# ProPrj_FaderBay_2025-03-18.net
KiCad netlist of a schematic drawn in EasyEDA Pro
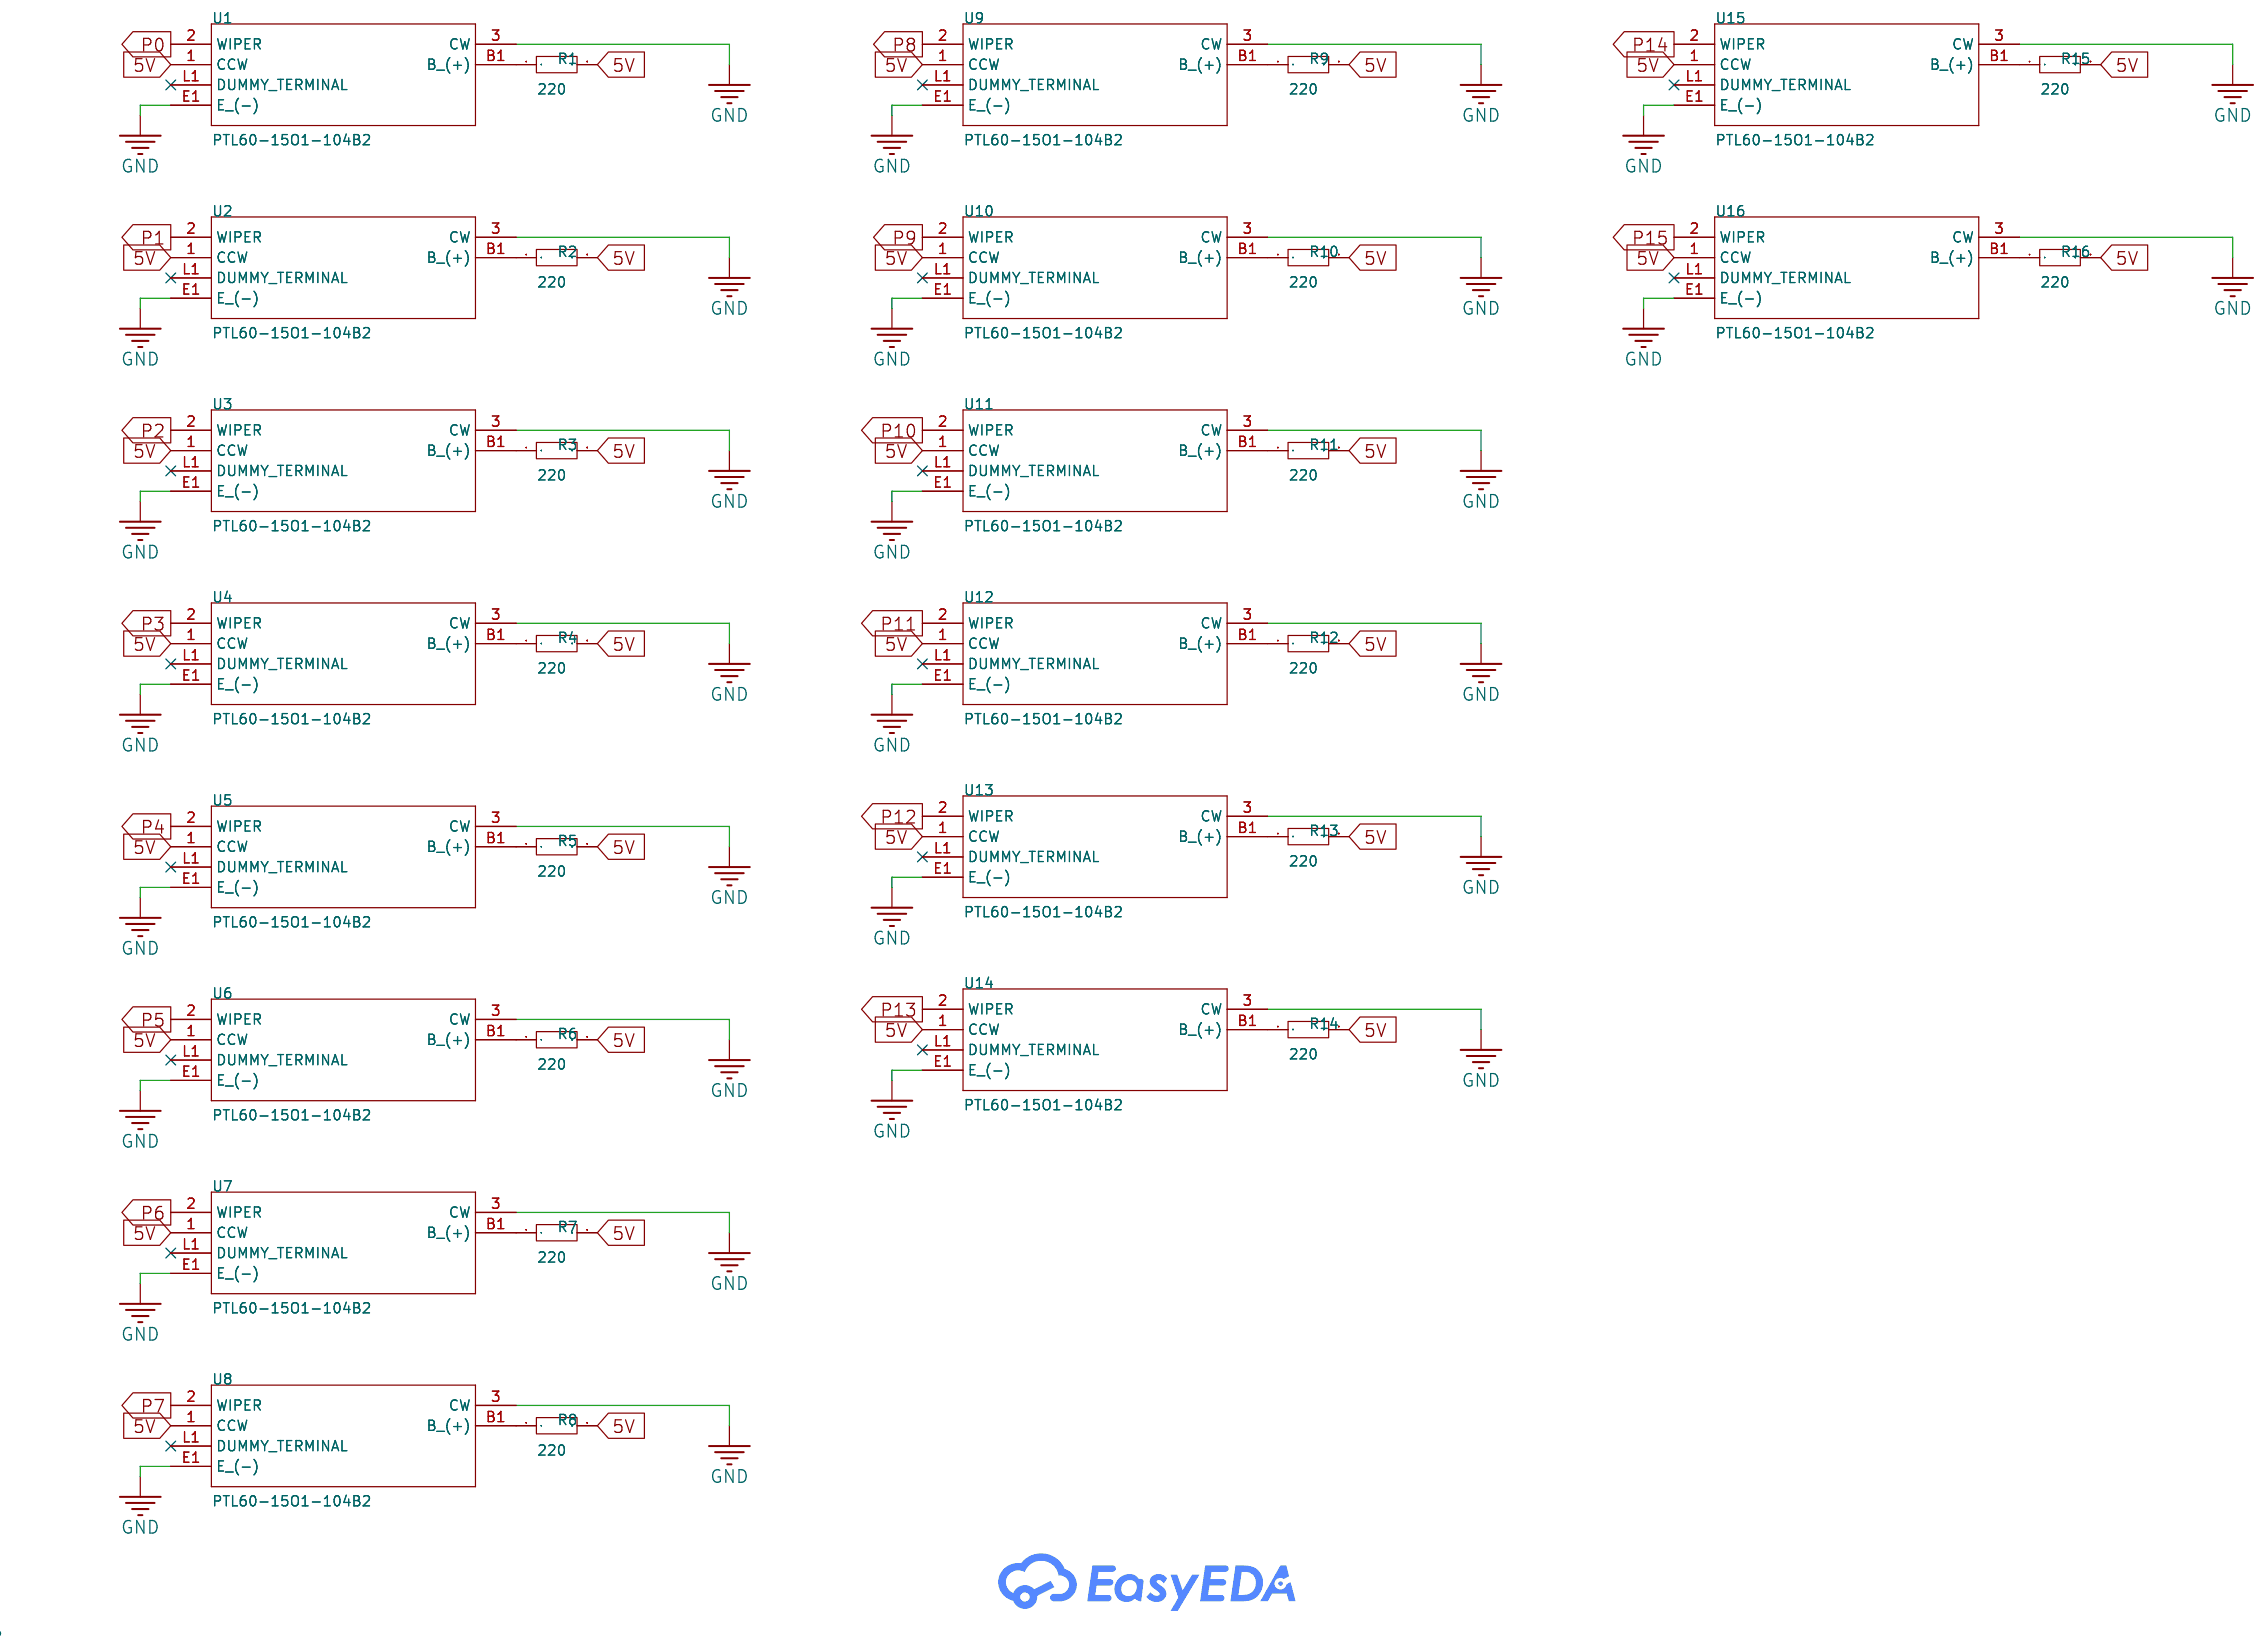
[diagram p0: P1]
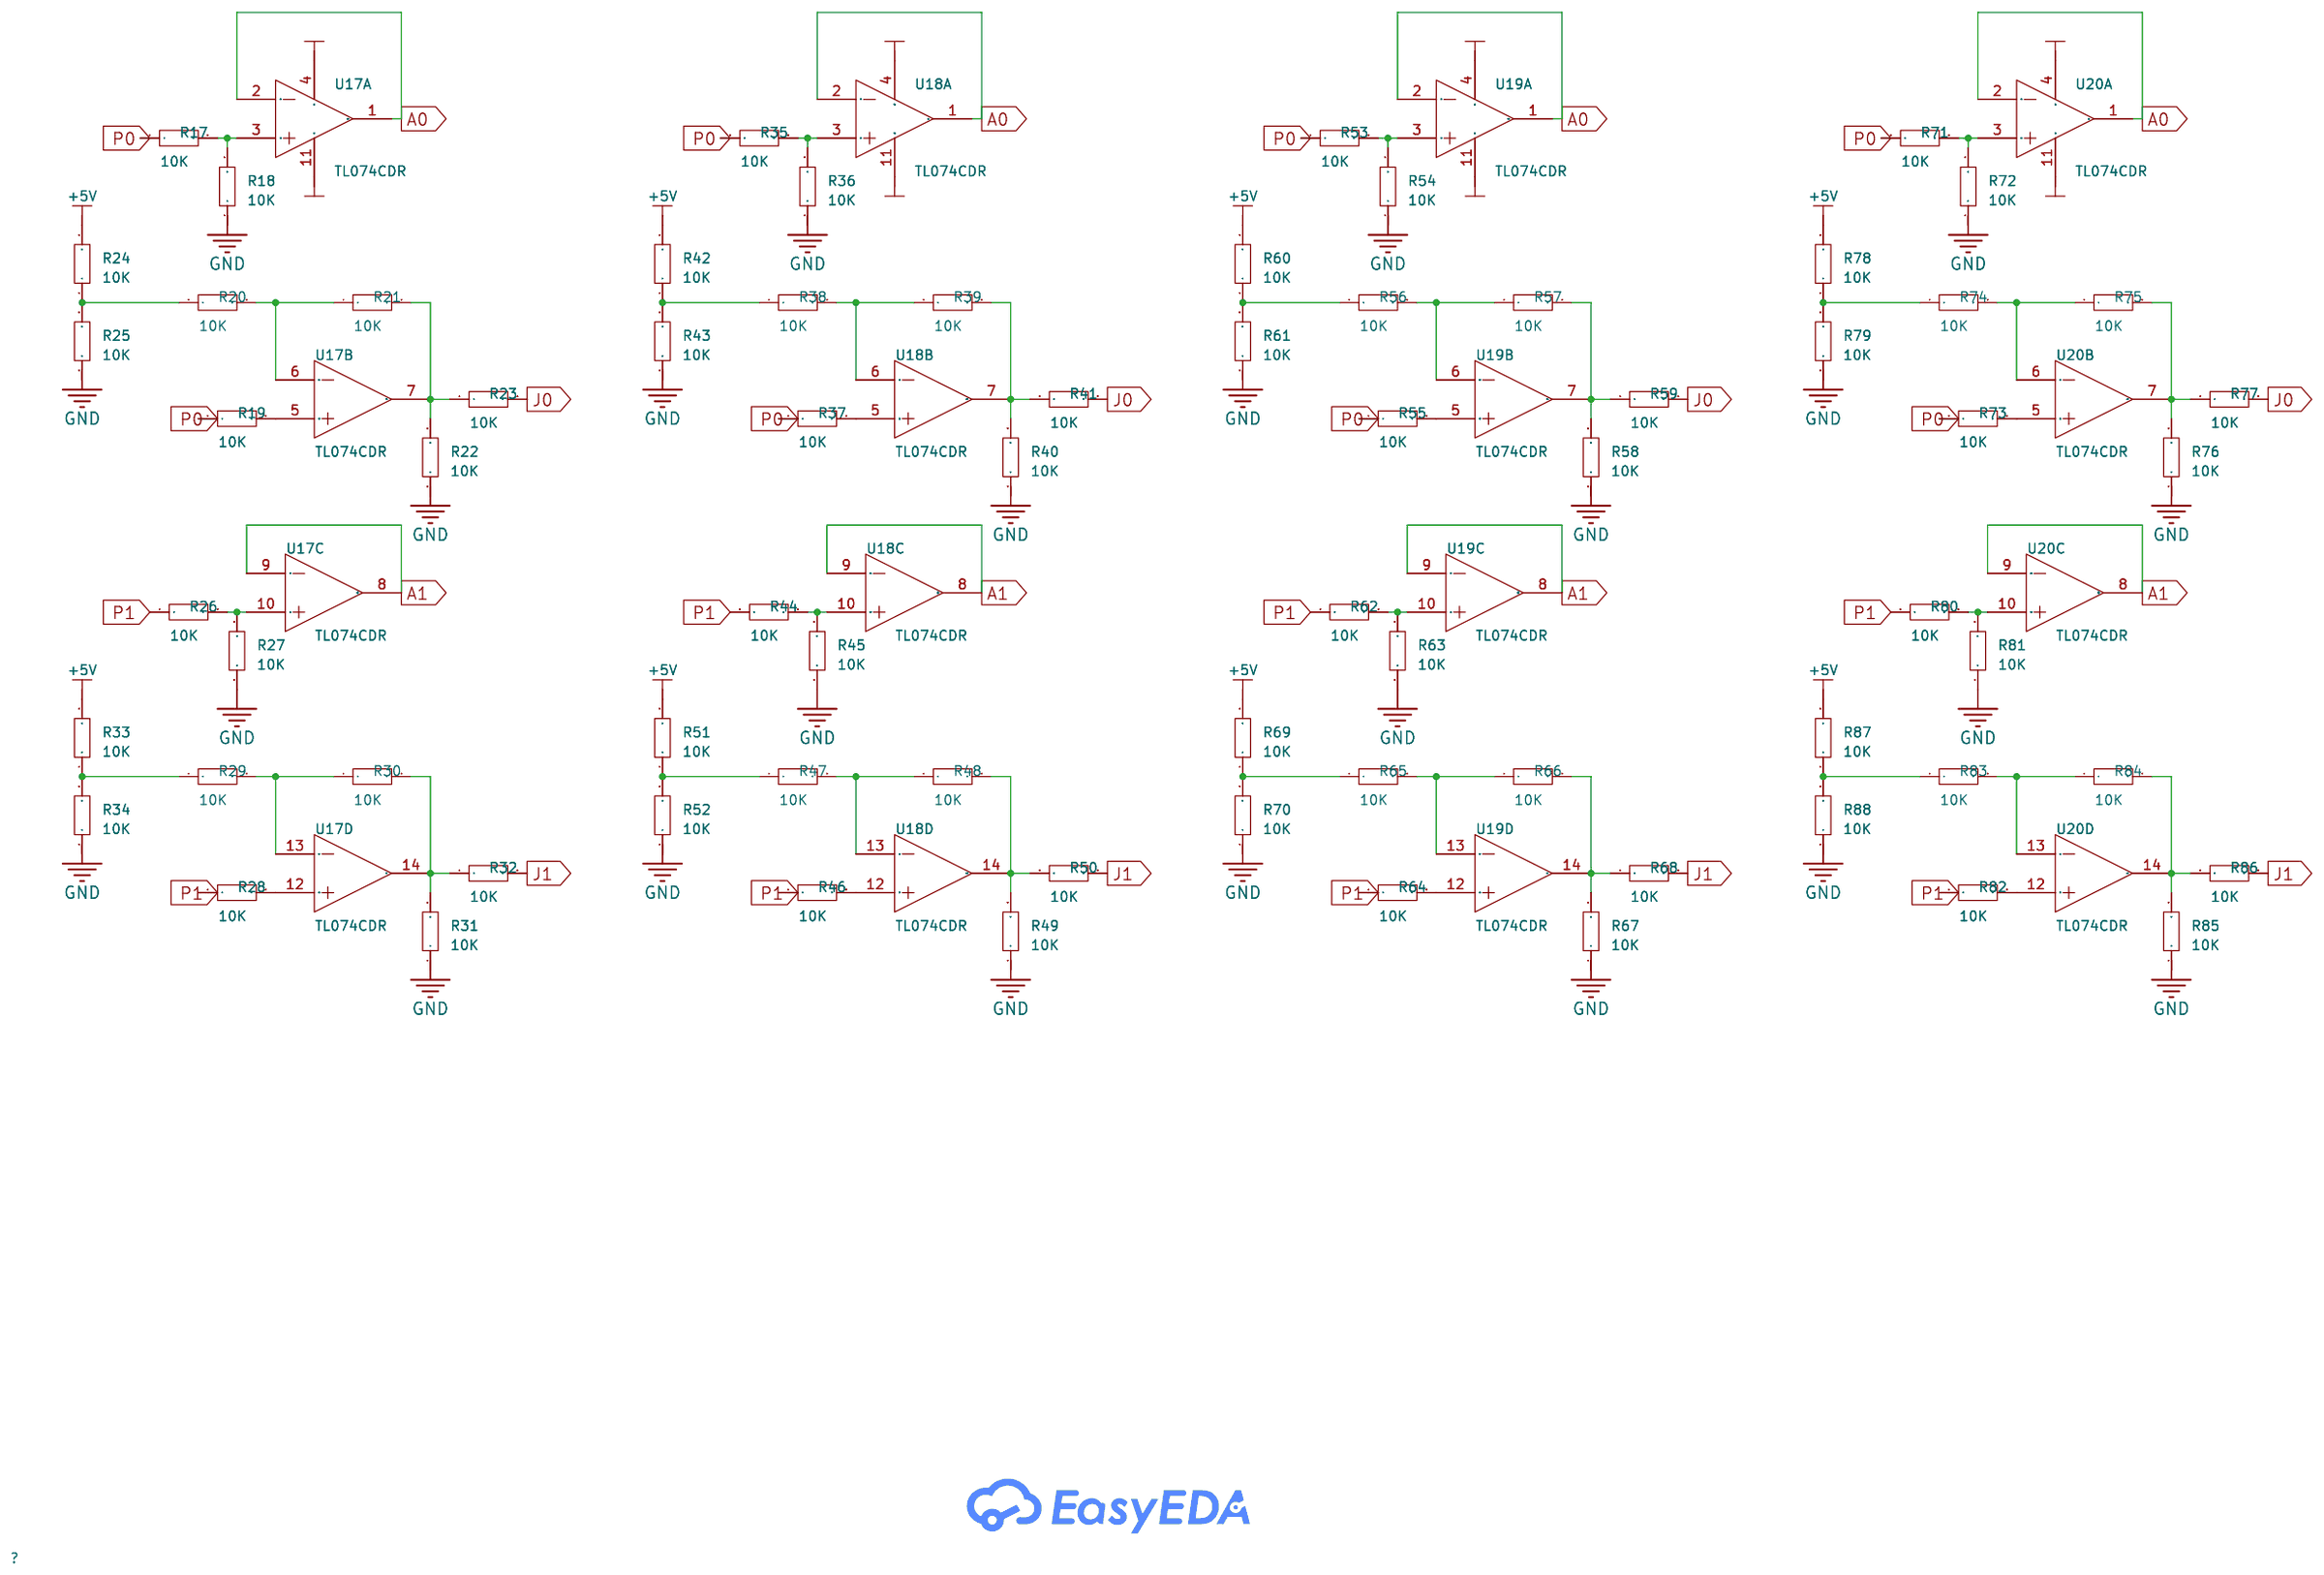
[diagram p1: P2]
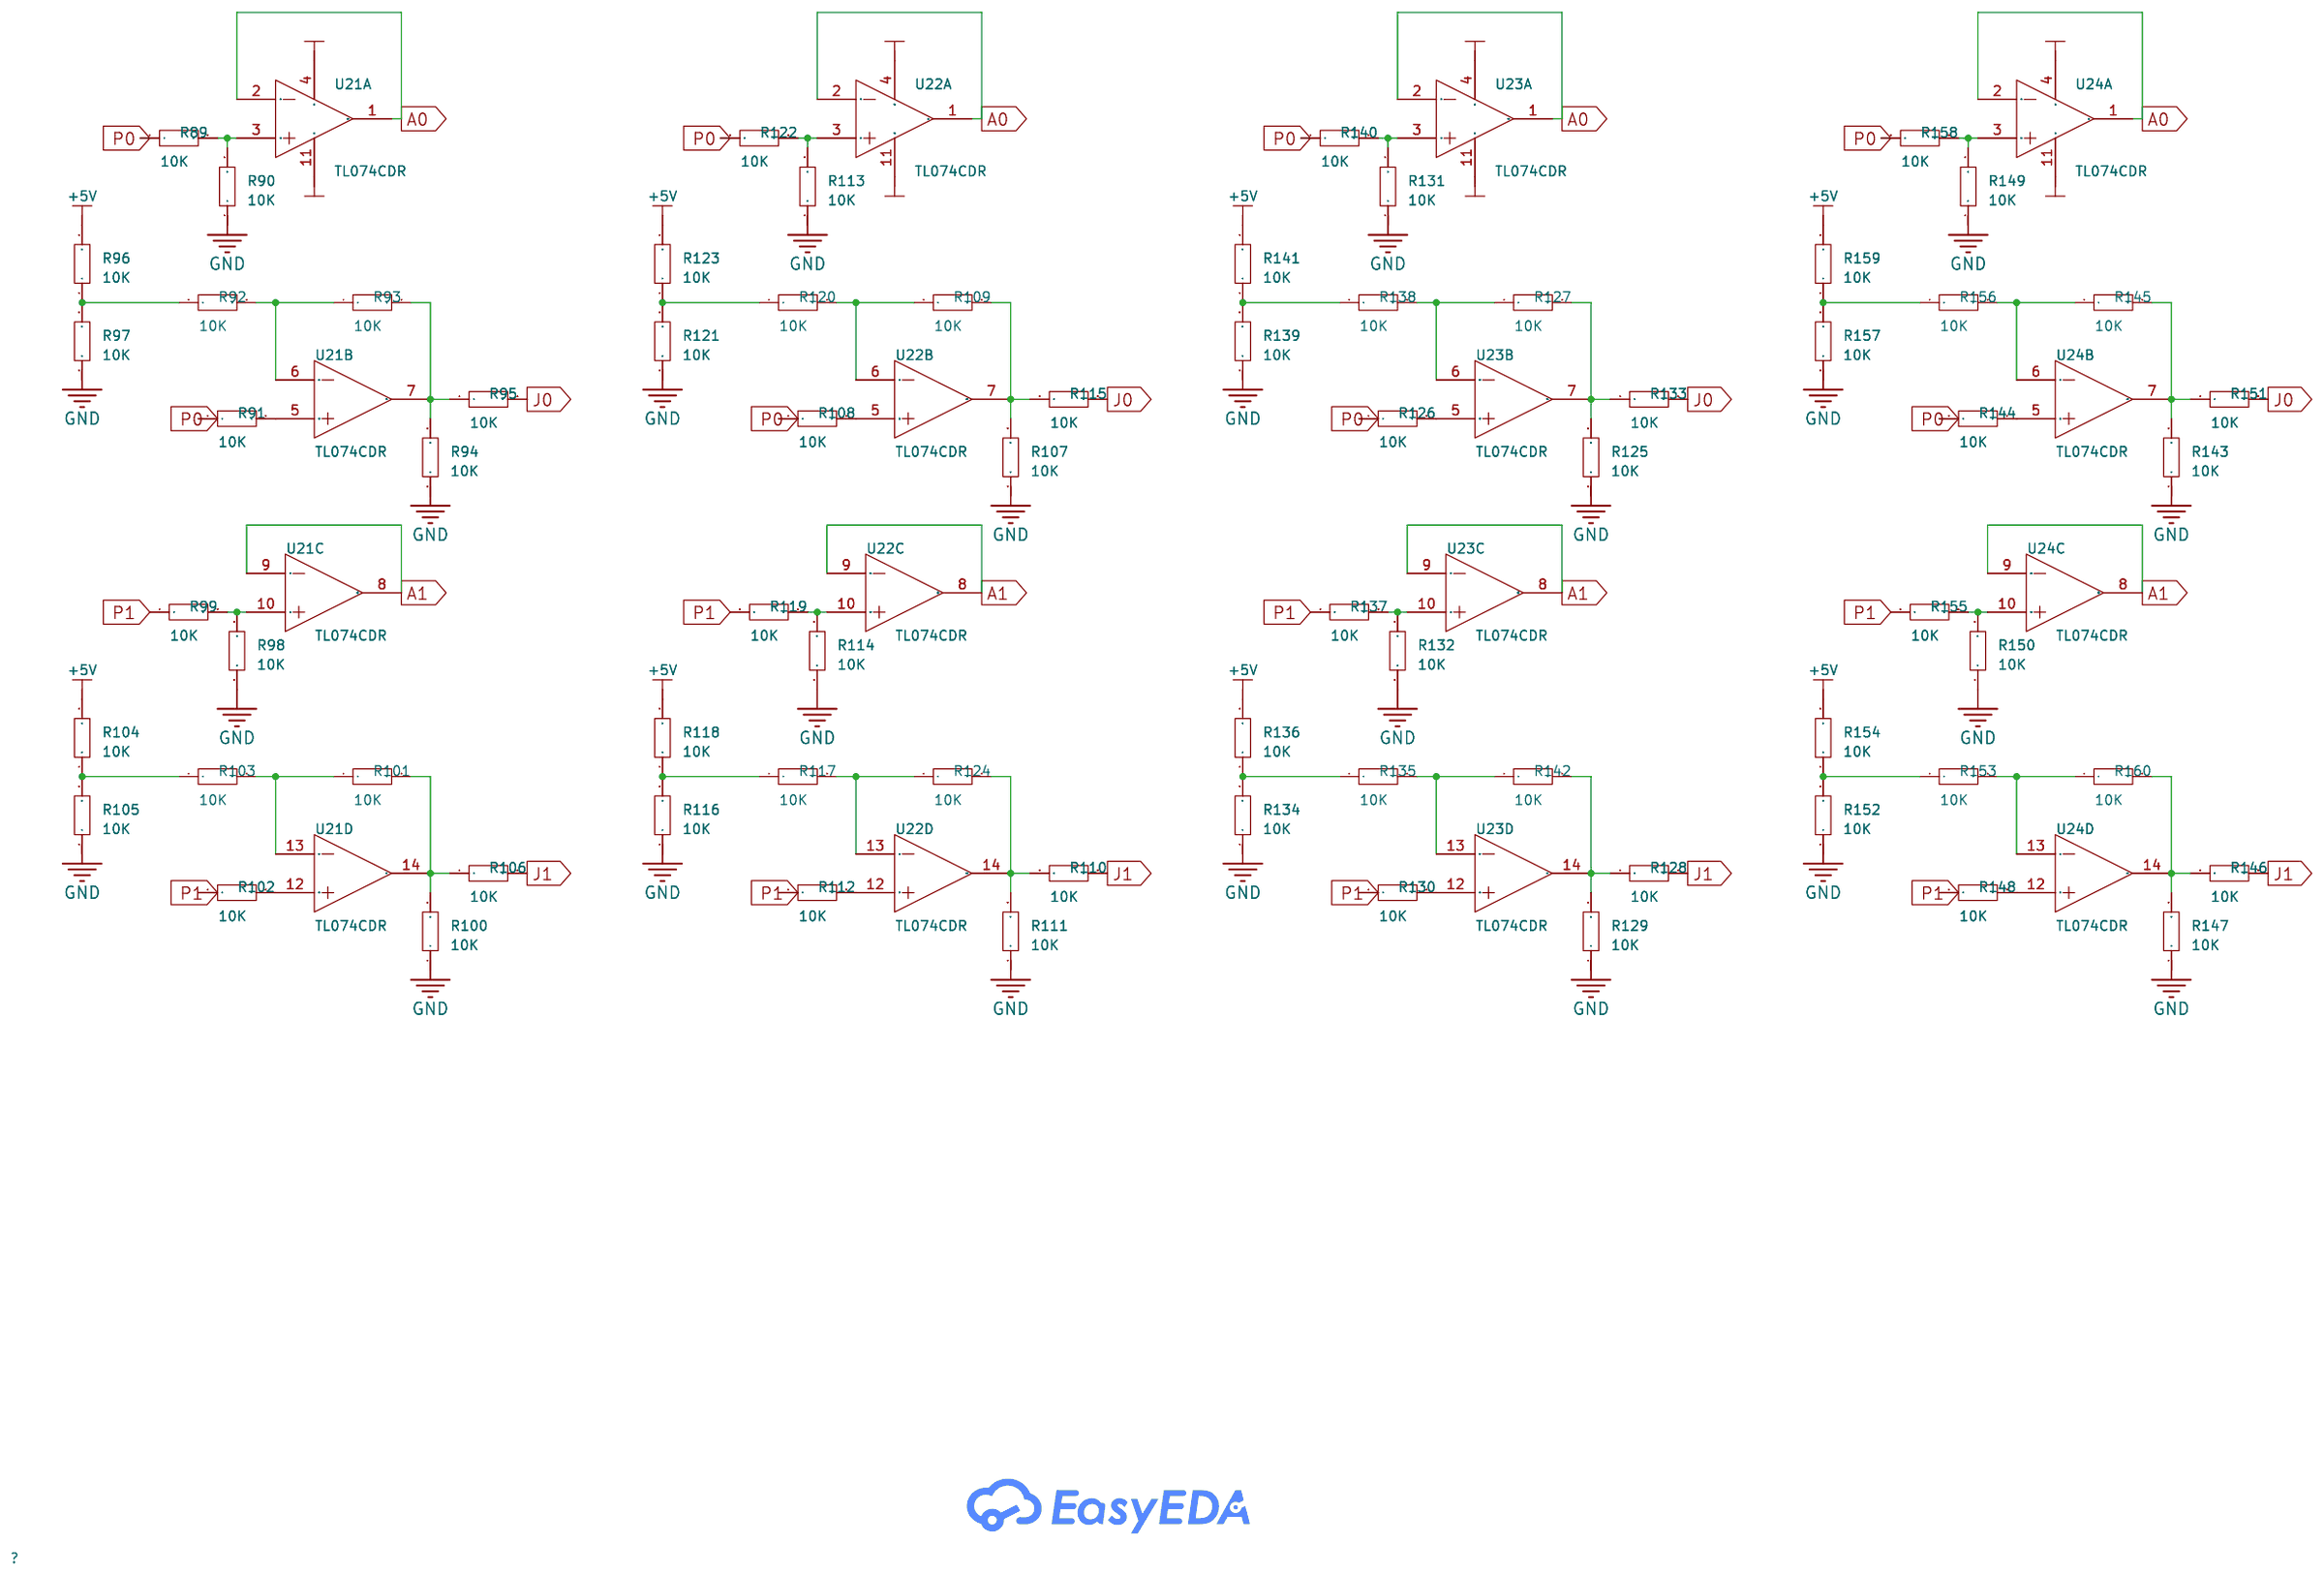
[diagram p2: P3]

(export (version "E")
  (design (tool "Eeschema 10.0.6"))
  (components
    (comp (ref "R1") (value "220") (footprint "easyedapro:R0603") (libsource (lib "easyedapro") (part "Res")))
    (comp (ref "R2") (value "220") (footprint "easyedapro:R0603") (libsource (lib "easyedapro") (part "Res")))
    (comp (ref "R3") (value "220") (footprint "easyedapro:R0603") (libsource (lib "easyedapro") (part "Res")))
    (comp (ref "R4") (value "220") (footprint "easyedapro:R0603") (libsource (lib "easyedapro") (part "Res")))
    (comp (ref "R5") (value "220") (footprint "easyedapro:R0603") (libsource (lib "easyedapro") (part "Res")))
    (comp (ref "R6") (value "220") (footprint "easyedapro:R0603") (libsource (lib "easyedapro") (part "Res")))
    (comp (ref "R7") (value "220") (footprint "easyedapro:R0603") (libsource (lib "easyedapro") (part "Res")))
    (comp (ref "R8") (value "220") (footprint "easyedapro:R0603") (libsource (lib "easyedapro") (part "Res")))
    (comp (ref "R9") (value "220") (footprint "easyedapro:R0603") (libsource (lib "easyedapro") (part "Res")))
    (comp (ref "R10")
      (value "220")
      (footprint "easyedapro:R0603")
      (libsource (lib "easyedapro") (part "Res"))
    )
    (comp (ref "R11")
      (value "220")
      (footprint "easyedapro:R0603")
      (libsource (lib "easyedapro") (part "Res"))
    )
    (comp (ref "R12")
      (value "220")
      (footprint "easyedapro:R0603")
      (libsource (lib "easyedapro") (part "Res"))
    )
    (comp (ref "R13")
      (value "220")
      (footprint "easyedapro:R0603")
      (libsource (lib "easyedapro") (part "Res"))
    )
    (comp (ref "R14")
      (value "220")
      (footprint "easyedapro:R0603")
      (libsource (lib "easyedapro") (part "Res"))
    )
    (comp (ref "R15")
      (value "220")
      (footprint "easyedapro:R0603")
      (libsource (lib "easyedapro") (part "Res"))
    )
    (comp (ref "R16")
      (value "220")
      (footprint "easyedapro:R0603")
      (libsource (lib "easyedapro") (part "Res"))
    )
    (comp (ref "U1")
      (value "PTL60-15O1-104B2")
      (footprint "easyedapro:PTL6015O1104B2")
      (libsource (lib "easyedapro") (part "PTL60-15O1-104B2"))
    )
    (comp (ref "U2")
      (value "PTL60-15O1-104B2")
      (footprint "easyedapro:PTL6015O1104B2")
      (libsource (lib "easyedapro") (part "PTL60-15O1-104B2"))
    )
    (comp (ref "U3")
      (value "PTL60-15O1-104B2")
      (footprint "easyedapro:PTL6015O1104B2")
      (libsource (lib "easyedapro") (part "PTL60-15O1-104B2"))
    )
    (comp (ref "U4")
      (value "PTL60-15O1-104B2")
      (footprint "easyedapro:PTL6015O1104B2")
      (libsource (lib "easyedapro") (part "PTL60-15O1-104B2"))
    )
    (comp (ref "U5")
      (value "PTL60-15O1-104B2")
      (footprint "easyedapro:PTL6015O1104B2")
      (libsource (lib "easyedapro") (part "PTL60-15O1-104B2"))
    )
    (comp (ref "U6")
      (value "PTL60-15O1-104B2")
      (footprint "easyedapro:PTL6015O1104B2")
      (libsource (lib "easyedapro") (part "PTL60-15O1-104B2"))
    )
    (comp (ref "U7")
      (value "PTL60-15O1-104B2")
      (footprint "easyedapro:PTL6015O1104B2")
      (libsource (lib "easyedapro") (part "PTL60-15O1-104B2"))
    )
    (comp (ref "U8")
      (value "PTL60-15O1-104B2")
      (footprint "easyedapro:PTL6015O1104B2")
      (libsource (lib "easyedapro") (part "PTL60-15O1-104B2"))
    )
    (comp (ref "U9")
      (value "PTL60-15O1-104B2")
      (footprint "easyedapro:PTL6015O1104B2")
      (libsource (lib "easyedapro") (part "PTL60-15O1-104B2"))
    )
    (comp (ref "U10")
      (value "PTL60-15O1-104B2")
      (footprint "easyedapro:PTL6015O1104B2")
      (libsource (lib "easyedapro") (part "PTL60-15O1-104B2"))
    )
    (comp (ref "U11")
      (value "PTL60-15O1-104B2")
      (footprint "easyedapro:PTL6015O1104B2")
      (libsource (lib "easyedapro") (part "PTL60-15O1-104B2"))
    )
    (comp (ref "U12")
      (value "PTL60-15O1-104B2")
      (footprint "easyedapro:PTL6015O1104B2")
      (libsource (lib "easyedapro") (part "PTL60-15O1-104B2"))
    )
    (comp (ref "U13")
      (value "PTL60-15O1-104B2")
      (footprint "easyedapro:PTL6015O1104B2")
      (libsource (lib "easyedapro") (part "PTL60-15O1-104B2"))
    )
    (comp (ref "U14")
      (value "PTL60-15O1-104B2")
      (footprint "easyedapro:PTL6015O1104B2")
      (libsource (lib "easyedapro") (part "PTL60-15O1-104B2"))
    )
    (comp (ref "U15")
      (value "PTL60-15O1-104B2")
      (footprint "easyedapro:PTL6015O1104B2")
      (libsource (lib "easyedapro") (part "PTL60-15O1-104B2"))
    )
    (comp (ref "U16")
      (value "PTL60-15O1-104B2")
      (footprint "easyedapro:PTL6015O1104B2")
      (libsource (lib "easyedapro") (part "PTL60-15O1-104B2"))
    )
    (comp (ref "R17")
      (value "10K")
      (footprint "easyedapro:R0603")
      (libsource (lib "easyedapro") (part "Res"))
    )
    (comp (ref "R18")
      (value "10K")
      (footprint "easyedapro:R0603")
      (libsource (lib "easyedapro") (part "Res"))
    )
    (comp (ref "R19")
      (value "10K")
      (footprint "easyedapro:R0603")
      (libsource (lib "easyedapro") (part "Res"))
    )
    (comp (ref "R20")
      (value "10K")
      (footprint "easyedapro:R0603")
      (libsource (lib "easyedapro") (part "Res"))
    )
    (comp (ref "R21")
      (value "10K")
      (footprint "easyedapro:R0603")
      (libsource (lib "easyedapro") (part "Res"))
    )
    (comp (ref "R22")
      (value "10K")
      (footprint "easyedapro:R0603")
      (libsource (lib "easyedapro") (part "Res"))
    )
    (comp (ref "R23")
      (value "10K")
      (footprint "easyedapro:R0603")
      (libsource (lib "easyedapro") (part "Res"))
    )
    (comp (ref "R24")
      (value "10K")
      (footprint "easyedapro:R0603")
      (libsource (lib "easyedapro") (part "Res"))
    )
    (comp (ref "R25")
      (value "10K")
      (footprint "easyedapro:R0603")
      (libsource (lib "easyedapro") (part "Res"))
    )
    (comp (ref "R26")
      (value "10K")
      (footprint "easyedapro:R0603")
      (libsource (lib "easyedapro") (part "Res"))
    )
    (comp (ref "R27")
      (value "10K")
      (footprint "easyedapro:R0603")
      (libsource (lib "easyedapro") (part "Res"))
    )
    (comp (ref "R28")
      (value "10K")
      (footprint "easyedapro:R0603")
      (libsource (lib "easyedapro") (part "Res"))
    )
    (comp (ref "R29")
      (value "10K")
      (footprint "easyedapro:R0603")
      (libsource (lib "easyedapro") (part "Res"))
    )
    (comp (ref "R30")
      (value "10K")
      (footprint "easyedapro:R0603")
      (libsource (lib "easyedapro") (part "Res"))
    )
    (comp (ref "R31")
      (value "10K")
      (footprint "easyedapro:R0603")
      (libsource (lib "easyedapro") (part "Res"))
    )
    (comp (ref "R32")
      (value "10K")
      (footprint "easyedapro:R0603")
      (libsource (lib "easyedapro") (part "Res"))
    )
    (comp (ref "R33")
      (value "10K")
      (footprint "easyedapro:R0603")
      (libsource (lib "easyedapro") (part "Res"))
    )
    (comp (ref "R34")
      (value "10K")
      (footprint "easyedapro:R0603")
      (libsource (lib "easyedapro") (part "Res"))
    )
    (comp (ref "R35")
      (value "10K")
      (footprint "easyedapro:R0603")
      (libsource (lib "easyedapro") (part "Res"))
    )
    (comp (ref "R36")
      (value "10K")
      (footprint "easyedapro:R0603")
      (libsource (lib "easyedapro") (part "Res"))
    )
    (comp (ref "R37")
      (value "10K")
      (footprint "easyedapro:R0603")
      (libsource (lib "easyedapro") (part "Res"))
    )
    (comp (ref "R38")
      (value "10K")
      (footprint "easyedapro:R0603")
      (libsource (lib "easyedapro") (part "Res"))
    )
    (comp (ref "R39")
      (value "10K")
      (footprint "easyedapro:R0603")
      (libsource (lib "easyedapro") (part "Res"))
    )
    (comp (ref "R40")
      (value "10K")
      (footprint "easyedapro:R0603")
      (libsource (lib "easyedapro") (part "Res"))
    )
    (comp (ref "R41")
      (value "10K")
      (footprint "easyedapro:R0603")
      (libsource (lib "easyedapro") (part "Res"))
    )
    (comp (ref "R42")
      (value "10K")
      (footprint "easyedapro:R0603")
      (libsource (lib "easyedapro") (part "Res"))
    )
    (comp (ref "R43")
      (value "10K")
      (footprint "easyedapro:R0603")
      (libsource (lib "easyedapro") (part "Res"))
    )
    (comp (ref "R44")
      (value "10K")
      (footprint "easyedapro:R0603")
      (libsource (lib "easyedapro") (part "Res"))
    )
    (comp (ref "R45")
      (value "10K")
      (footprint "easyedapro:R0603")
      (libsource (lib "easyedapro") (part "Res"))
    )
    (comp (ref "R46")
      (value "10K")
      (footprint "easyedapro:R0603")
      (libsource (lib "easyedapro") (part "Res"))
    )
    (comp (ref "R47")
      (value "10K")
      (footprint "easyedapro:R0603")
      (libsource (lib "easyedapro") (part "Res"))
    )
    (comp (ref "R48")
      (value "10K")
      (footprint "easyedapro:R0603")
      (libsource (lib "easyedapro") (part "Res"))
    )
    (comp (ref "R49")
      (value "10K")
      (footprint "easyedapro:R0603")
      (libsource (lib "easyedapro") (part "Res"))
    )
    (comp (ref "R50")
      (value "10K")
      (footprint "easyedapro:R0603")
      (libsource (lib "easyedapro") (part "Res"))
    )
    (comp (ref "R51")
      (value "10K")
      (footprint "easyedapro:R0603")
      (libsource (lib "easyedapro") (part "Res"))
    )
    (comp (ref "R52")
      (value "10K")
      (footprint "easyedapro:R0603")
      (libsource (lib "easyedapro") (part "Res"))
    )
    (comp (ref "R53")
      (value "10K")
      (footprint "easyedapro:R0603")
      (libsource (lib "easyedapro") (part "Res"))
    )
    (comp (ref "R54")
      (value "10K")
      (footprint "easyedapro:R0603")
      (libsource (lib "easyedapro") (part "Res"))
    )
    (comp (ref "R55")
      (value "10K")
      (footprint "easyedapro:R0603")
      (libsource (lib "easyedapro") (part "Res"))
    )
    (comp (ref "R56")
      (value "10K")
      (footprint "easyedapro:R0603")
      (libsource (lib "easyedapro") (part "Res"))
    )
    (comp (ref "R57")
      (value "10K")
      (footprint "easyedapro:R0603")
      (libsource (lib "easyedapro") (part "Res"))
    )
    (comp (ref "R58")
      (value "10K")
      (footprint "easyedapro:R0603")
      (libsource (lib "easyedapro") (part "Res"))
    )
    (comp (ref "R59")
      (value "10K")
      (footprint "easyedapro:R0603")
      (libsource (lib "easyedapro") (part "Res"))
    )
    (comp (ref "R60")
      (value "10K")
      (footprint "easyedapro:R0603")
      (libsource (lib "easyedapro") (part "Res"))
    )
    (comp (ref "R61")
      (value "10K")
      (footprint "easyedapro:R0603")
      (libsource (lib "easyedapro") (part "Res"))
    )
    (comp (ref "R62")
      (value "10K")
      (footprint "easyedapro:R0603")
      (libsource (lib "easyedapro") (part "Res"))
    )
    (comp (ref "R63")
      (value "10K")
      (footprint "easyedapro:R0603")
      (libsource (lib "easyedapro") (part "Res"))
    )
    (comp (ref "R64")
      (value "10K")
      (footprint "easyedapro:R0603")
      (libsource (lib "easyedapro") (part "Res"))
    )
    (comp (ref "R65")
      (value "10K")
      (footprint "easyedapro:R0603")
      (libsource (lib "easyedapro") (part "Res"))
    )
    (comp (ref "R66")
      (value "10K")
      (footprint "easyedapro:R0603")
      (libsource (lib "easyedapro") (part "Res"))
    )
    (comp (ref "R67")
      (value "10K")
      (footprint "easyedapro:R0603")
      (libsource (lib "easyedapro") (part "Res"))
    )
    (comp (ref "R68")
      (value "10K")
      (footprint "easyedapro:R0603")
      (libsource (lib "easyedapro") (part "Res"))
    )
    (comp (ref "R69")
      (value "10K")
      (footprint "easyedapro:R0603")
      (libsource (lib "easyedapro") (part "Res"))
    )
    (comp (ref "R70")
      (value "10K")
      (footprint "easyedapro:R0603")
      (libsource (lib "easyedapro") (part "Res"))
    )
    (comp (ref "R71")
      (value "10K")
      (footprint "easyedapro:R0603")
      (libsource (lib "easyedapro") (part "Res"))
    )
    (comp (ref "R72")
      (value "10K")
      (footprint "easyedapro:R0603")
      (libsource (lib "easyedapro") (part "Res"))
    )
    (comp (ref "R73")
      (value "10K")
      (footprint "easyedapro:R0603")
      (libsource (lib "easyedapro") (part "Res"))
    )
    (comp (ref "R74")
      (value "10K")
      (footprint "easyedapro:R0603")
      (libsource (lib "easyedapro") (part "Res"))
    )
    (comp (ref "R75")
      (value "10K")
      (footprint "easyedapro:R0603")
      (libsource (lib "easyedapro") (part "Res"))
    )
    (comp (ref "R76")
      (value "10K")
      (footprint "easyedapro:R0603")
      (libsource (lib "easyedapro") (part "Res"))
    )
    (comp (ref "R77")
      (value "10K")
      (footprint "easyedapro:R0603")
      (libsource (lib "easyedapro") (part "Res"))
    )
    (comp (ref "R78")
      (value "10K")
      (footprint "easyedapro:R0603")
      (libsource (lib "easyedapro") (part "Res"))
    )
    (comp (ref "R79")
      (value "10K")
      (footprint "easyedapro:R0603")
      (libsource (lib "easyedapro") (part "Res"))
    )
    (comp (ref "R80")
      (value "10K")
      (footprint "easyedapro:R0603")
      (libsource (lib "easyedapro") (part "Res"))
    )
    (comp (ref "R81")
      (value "10K")
      (footprint "easyedapro:R0603")
      (libsource (lib "easyedapro") (part "Res"))
    )
    (comp (ref "R82")
      (value "10K")
      (footprint "easyedapro:R0603")
      (libsource (lib "easyedapro") (part "Res"))
    )
    (comp (ref "R83")
      (value "10K")
      (footprint "easyedapro:R0603")
      (libsource (lib "easyedapro") (part "Res"))
    )
    (comp (ref "R84")
      (value "10K")
      (footprint "easyedapro:R0603")
      (libsource (lib "easyedapro") (part "Res"))
    )
    (comp (ref "R85")
      (value "10K")
      (footprint "easyedapro:R0603")
      (libsource (lib "easyedapro") (part "Res"))
    )
    (comp (ref "R86")
      (value "10K")
      (footprint "easyedapro:R0603")
      (libsource (lib "easyedapro") (part "Res"))
    )
    (comp (ref "R87")
      (value "10K")
      (footprint "easyedapro:R0603")
      (libsource (lib "easyedapro") (part "Res"))
    )
    (comp (ref "R88")
      (value "10K")
      (footprint "easyedapro:R0603")
      (libsource (lib "easyedapro") (part "Res"))
    )
    (comp (ref "U17")
      (value "TL074CDR")
      (footprint "easyedapro:SOIC-14_L8.7-W3.9-P1.27-LS6.0-BL")
      (fields (field (name "Manufacturer") "TI(德州仪器)"))
      (libsource (lib "easyedapro") (part "TL074CDR"))
    )
    (comp (ref "U18")
      (value "TL074CDR")
      (footprint "easyedapro:SOIC-14_L8.7-W3.9-P1.27-LS6.0-BL")
      (fields (field (name "Manufacturer") "TI(德州仪器)"))
      (libsource (lib "easyedapro") (part "TL074CDR"))
    )
    (comp (ref "U19")
      (value "TL074CDR")
      (footprint "easyedapro:SOIC-14_L8.7-W3.9-P1.27-LS6.0-BL")
      (fields (field (name "Manufacturer") "TI(德州仪器)"))
      (libsource (lib "easyedapro") (part "TL074CDR"))
    )
    (comp (ref "U20")
      (value "TL074CDR")
      (footprint "easyedapro:SOIC-14_L8.7-W3.9-P1.27-LS6.0-BL")
      (fields (field (name "Manufacturer") "TI(德州仪器)"))
      (libsource (lib "easyedapro") (part "TL074CDR"))
    )
    (comp (ref "R89")
      (value "10K")
      (footprint "easyedapro:R0603")
      (libsource (lib "easyedapro") (part "Res"))
    )
    (comp (ref "R90")
      (value "10K")
      (footprint "easyedapro:R0603")
      (libsource (lib "easyedapro") (part "Res"))
    )
    (comp (ref "R91")
      (value "10K")
      (footprint "easyedapro:R0603")
      (libsource (lib "easyedapro") (part "Res"))
    )
    (comp (ref "R92")
      (value "10K")
      (footprint "easyedapro:R0603")
      (libsource (lib "easyedapro") (part "Res"))
    )
    (comp (ref "R93")
      (value "10K")
      (footprint "easyedapro:R0603")
      (libsource (lib "easyedapro") (part "Res"))
    )
    (comp (ref "R94")
      (value "10K")
      (footprint "easyedapro:R0603")
      (libsource (lib "easyedapro") (part "Res"))
    )
    (comp (ref "R95")
      (value "10K")
      (footprint "easyedapro:R0603")
      (libsource (lib "easyedapro") (part "Res"))
    )
    (comp (ref "R96")
      (value "10K")
      (footprint "easyedapro:R0603")
      (libsource (lib "easyedapro") (part "Res"))
    )
    (comp (ref "R97")
      (value "10K")
      (footprint "easyedapro:R0603")
      (libsource (lib "easyedapro") (part "Res"))
    )
    (comp (ref "R98")
      (value "10K")
      (footprint "easyedapro:R0603")
      (libsource (lib "easyedapro") (part "Res"))
    )
    (comp (ref "R99")
      (value "10K")
      (footprint "easyedapro:R0603")
      (libsource (lib "easyedapro") (part "Res"))
    )
    (comp (ref "R100")
      (value "10K")
      (footprint "easyedapro:R0603")
      (libsource (lib "easyedapro") (part "Res"))
    )
    (comp (ref "R101")
      (value "10K")
      (footprint "easyedapro:R0603")
      (libsource (lib "easyedapro") (part "Res"))
    )
    (comp (ref "R102")
      (value "10K")
      (footprint "easyedapro:R0603")
      (libsource (lib "easyedapro") (part "Res"))
    )
    (comp (ref "R103")
      (value "10K")
      (footprint "easyedapro:R0603")
      (libsource (lib "easyedapro") (part "Res"))
    )
    (comp (ref "R104")
      (value "10K")
      (footprint "easyedapro:R0603")
      (libsource (lib "easyedapro") (part "Res"))
    )
    (comp (ref "R105")
      (value "10K")
      (footprint "easyedapro:R0603")
      (libsource (lib "easyedapro") (part "Res"))
    )
    (comp (ref "R106")
      (value "10K")
      (footprint "easyedapro:R0603")
      (libsource (lib "easyedapro") (part "Res"))
    )
    (comp (ref "R107")
      (value "10K")
      (footprint "easyedapro:R0603")
      (libsource (lib "easyedapro") (part "Res"))
    )
    (comp (ref "R108")
      (value "10K")
      (footprint "easyedapro:R0603")
      (libsource (lib "easyedapro") (part "Res"))
    )
    (comp (ref "R109")
      (value "10K")
      (footprint "easyedapro:R0603")
      (libsource (lib "easyedapro") (part "Res"))
    )
    (comp (ref "R110")
      (value "10K")
      (footprint "easyedapro:R0603")
      (libsource (lib "easyedapro") (part "Res"))
    )
    (comp (ref "R111")
      (value "10K")
      (footprint "easyedapro:R0603")
      (libsource (lib "easyedapro") (part "Res"))
    )
    (comp (ref "R112")
      (value "10K")
      (footprint "easyedapro:R0603")
      (libsource (lib "easyedapro") (part "Res"))
    )
    (comp (ref "R113")
      (value "10K")
      (footprint "easyedapro:R0603")
      (libsource (lib "easyedapro") (part "Res"))
    )
    (comp (ref "R114")
      (value "10K")
      (footprint "easyedapro:R0603")
      (libsource (lib "easyedapro") (part "Res"))
    )
    (comp (ref "R115")
      (value "10K")
      (footprint "easyedapro:R0603")
      (libsource (lib "easyedapro") (part "Res"))
    )
    (comp (ref "R116")
      (value "10K")
      (footprint "easyedapro:R0603")
      (libsource (lib "easyedapro") (part "Res"))
    )
    (comp (ref "R117")
      (value "10K")
      (footprint "easyedapro:R0603")
      (libsource (lib "easyedapro") (part "Res"))
    )
    (comp (ref "R118")
      (value "10K")
      (footprint "easyedapro:R0603")
      (libsource (lib "easyedapro") (part "Res"))
    )
    (comp (ref "R119")
      (value "10K")
      (footprint "easyedapro:R0603")
      (libsource (lib "easyedapro") (part "Res"))
    )
    (comp (ref "R120")
      (value "10K")
      (footprint "easyedapro:R0603")
      (libsource (lib "easyedapro") (part "Res"))
    )
    (comp (ref "R121")
      (value "10K")
      (footprint "easyedapro:R0603")
      (libsource (lib "easyedapro") (part "Res"))
    )
    (comp (ref "R122")
      (value "10K")
      (footprint "easyedapro:R0603")
      (libsource (lib "easyedapro") (part "Res"))
    )
    (comp (ref "R123")
      (value "10K")
      (footprint "easyedapro:R0603")
      (libsource (lib "easyedapro") (part "Res"))
    )
    (comp (ref "R124")
      (value "10K")
      (footprint "easyedapro:R0603")
      (libsource (lib "easyedapro") (part "Res"))
    )
    (comp (ref "R125")
      (value "10K")
      (footprint "easyedapro:R0603")
      (libsource (lib "easyedapro") (part "Res"))
    )
    (comp (ref "R126")
      (value "10K")
      (footprint "easyedapro:R0603")
      (libsource (lib "easyedapro") (part "Res"))
    )
    (comp (ref "R127")
      (value "10K")
      (footprint "easyedapro:R0603")
      (libsource (lib "easyedapro") (part "Res"))
    )
    (comp (ref "R128")
      (value "10K")
      (footprint "easyedapro:R0603")
      (libsource (lib "easyedapro") (part "Res"))
    )
    (comp (ref "R129")
      (value "10K")
      (footprint "easyedapro:R0603")
      (libsource (lib "easyedapro") (part "Res"))
    )
    (comp (ref "R130")
      (value "10K")
      (footprint "easyedapro:R0603")
      (libsource (lib "easyedapro") (part "Res"))
    )
    (comp (ref "R131")
      (value "10K")
      (footprint "easyedapro:R0603")
      (libsource (lib "easyedapro") (part "Res"))
    )
    (comp (ref "R132")
      (value "10K")
      (footprint "easyedapro:R0603")
      (libsource (lib "easyedapro") (part "Res"))
    )
    (comp (ref "R133")
      (value "10K")
      (footprint "easyedapro:R0603")
      (libsource (lib "easyedapro") (part "Res"))
    )
    (comp (ref "R134")
      (value "10K")
      (footprint "easyedapro:R0603")
      (libsource (lib "easyedapro") (part "Res"))
    )
    (comp (ref "R135")
      (value "10K")
      (footprint "easyedapro:R0603")
      (libsource (lib "easyedapro") (part "Res"))
    )
    (comp (ref "R136")
      (value "10K")
      (footprint "easyedapro:R0603")
      (libsource (lib "easyedapro") (part "Res"))
    )
    (comp (ref "R137")
      (value "10K")
      (footprint "easyedapro:R0603")
      (libsource (lib "easyedapro") (part "Res"))
    )
    (comp (ref "R138")
      (value "10K")
      (footprint "easyedapro:R0603")
      (libsource (lib "easyedapro") (part "Res"))
    )
    (comp (ref "R139")
      (value "10K")
      (footprint "easyedapro:R0603")
      (libsource (lib "easyedapro") (part "Res"))
    )
    (comp (ref "R140")
      (value "10K")
      (footprint "easyedapro:R0603")
      (libsource (lib "easyedapro") (part "Res"))
    )
    (comp (ref "R141")
      (value "10K")
      (footprint "easyedapro:R0603")
      (libsource (lib "easyedapro") (part "Res"))
    )
    (comp (ref "R142")
      (value "10K")
      (footprint "easyedapro:R0603")
      (libsource (lib "easyedapro") (part "Res"))
    )
    (comp (ref "R143")
      (value "10K")
      (footprint "easyedapro:R0603")
      (libsource (lib "easyedapro") (part "Res"))
    )
    (comp (ref "R144")
      (value "10K")
      (footprint "easyedapro:R0603")
      (libsource (lib "easyedapro") (part "Res"))
    )
    (comp (ref "R145")
      (value "10K")
      (footprint "easyedapro:R0603")
      (libsource (lib "easyedapro") (part "Res"))
    )
    (comp (ref "R146")
      (value "10K")
      (footprint "easyedapro:R0603")
      (libsource (lib "easyedapro") (part "Res"))
    )
    (comp (ref "R147")
      (value "10K")
      (footprint "easyedapro:R0603")
      (libsource (lib "easyedapro") (part "Res"))
    )
    (comp (ref "R148")
      (value "10K")
      (footprint "easyedapro:R0603")
      (libsource (lib "easyedapro") (part "Res"))
    )
    (comp (ref "R149")
      (value "10K")
      (footprint "easyedapro:R0603")
      (libsource (lib "easyedapro") (part "Res"))
    )
    (comp (ref "R150")
      (value "10K")
      (footprint "easyedapro:R0603")
      (libsource (lib "easyedapro") (part "Res"))
    )
    (comp (ref "R151")
      (value "10K")
      (footprint "easyedapro:R0603")
      (libsource (lib "easyedapro") (part "Res"))
    )
    (comp (ref "R152")
      (value "10K")
      (footprint "easyedapro:R0603")
      (libsource (lib "easyedapro") (part "Res"))
    )
    (comp (ref "R153")
      (value "10K")
      (footprint "easyedapro:R0603")
      (libsource (lib "easyedapro") (part "Res"))
    )
    (comp (ref "R154")
      (value "10K")
      (footprint "easyedapro:R0603")
      (libsource (lib "easyedapro") (part "Res"))
    )
    (comp (ref "R155")
      (value "10K")
      (footprint "easyedapro:R0603")
      (libsource (lib "easyedapro") (part "Res"))
    )
    (comp (ref "R156")
      (value "10K")
      (footprint "easyedapro:R0603")
      (libsource (lib "easyedapro") (part "Res"))
    )
    (comp (ref "R157")
      (value "10K")
      (footprint "easyedapro:R0603")
      (libsource (lib "easyedapro") (part "Res"))
    )
    (comp (ref "R158")
      (value "10K")
      (footprint "easyedapro:R0603")
      (libsource (lib "easyedapro") (part "Res"))
    )
    (comp (ref "R159")
      (value "10K")
      (footprint "easyedapro:R0603")
      (libsource (lib "easyedapro") (part "Res"))
    )
    (comp (ref "R160")
      (value "10K")
      (footprint "easyedapro:R0603")
      (libsource (lib "easyedapro") (part "Res"))
    )
    (comp (ref "U21")
      (value "TL074CDR")
      (footprint "easyedapro:SOIC-14_L8.7-W3.9-P1.27-LS6.0-BL")
      (fields (field (name "Manufacturer") "TI(德州仪器)"))
      (libsource (lib "easyedapro") (part "TL074CDR"))
    )
    (comp (ref "U22")
      (value "TL074CDR")
      (footprint "easyedapro:SOIC-14_L8.7-W3.9-P1.27-LS6.0-BL")
      (fields (field (name "Manufacturer") "TI(德州仪器)"))
      (libsource (lib "easyedapro") (part "TL074CDR"))
    )
    (comp (ref "U23")
      (value "TL074CDR")
      (footprint "easyedapro:SOIC-14_L8.7-W3.9-P1.27-LS6.0-BL")
      (fields (field (name "Manufacturer") "TI(德州仪器)"))
      (libsource (lib "easyedapro") (part "TL074CDR"))
    )
    (comp (ref "U24")
      (value "TL074CDR")
      (footprint "easyedapro:SOIC-14_L8.7-W3.9-P1.27-LS6.0-BL")
      (fields (field (name "Manufacturer") "TI(德州仪器)"))
      (libsource (lib "easyedapro") (part "TL074CDR"))
    )
  )
  (nets
    (net (code "1") (name "+5V") (class "Default")
      (node (ref "R104") (pin "2") (pinfunction "2_2") (pintype "input"))
      (node (ref "R118") (pin "2") (pinfunction "2_2") (pintype "input"))
      (node (ref "R123") (pin "2") (pinfunction "2_2") (pintype "input"))
      (node (ref "R136") (pin "2") (pinfunction "2_2") (pintype "input"))
      (node (ref "R141") (pin "2") (pinfunction "2_2") (pintype "input"))
      (node (ref "R154") (pin "2") (pinfunction "2_2") (pintype "input"))
      (node (ref "R159") (pin "2") (pinfunction "2_2") (pintype "input"))
      (node (ref "R24") (pin "2") (pinfunction "2_2") (pintype "input"))
      (node (ref "R33") (pin "2") (pinfunction "2_2") (pintype "input"))
      (node (ref "R42") (pin "2") (pinfunction "2_2") (pintype "input"))
      (node (ref "R51") (pin "2") (pinfunction "2_2") (pintype "input"))
      (node (ref "R60") (pin "2") (pinfunction "2_2") (pintype "input"))
      (node (ref "R69") (pin "2") (pinfunction "2_2") (pintype "input"))
      (node (ref "R78") (pin "2") (pinfunction "2_2") (pintype "input"))
      (node (ref "R87") (pin "2") (pinfunction "2_2") (pintype "input"))
      (node (ref "R96") (pin "2") (pinfunction "2_2") (pintype "input"))
    )
    (net (code "2") (name "+12V") (class "Default")
      (node (ref "U17") (pin "4") (pinfunction "VCC+_4") (pintype "unspecified"))
      (node (ref "U18") (pin "4") (pinfunction "VCC+_4") (pintype "unspecified"))
      (node (ref "U19") (pin "4") (pinfunction "VCC+_4") (pintype "unspecified"))
      (node (ref "U20") (pin "4") (pinfunction "VCC+_4") (pintype "unspecified"))
      (node (ref "U21") (pin "4") (pinfunction "VCC+_4") (pintype "unspecified"))
      (node (ref "U22") (pin "4") (pinfunction "VCC+_4") (pintype "unspecified"))
      (node (ref "U23") (pin "4") (pinfunction "VCC+_4") (pintype "unspecified"))
      (node (ref "U24") (pin "4") (pinfunction "VCC+_4") (pintype "unspecified"))
    )
    (net (code "3") (name "-12V") (class "Default")
      (node (ref "U17") (pin "11") (pinfunction "VCC-_11") (pintype "unspecified"))
      (node (ref "U18") (pin "11") (pinfunction "VCC-_11") (pintype "unspecified"))
      (node (ref "U19") (pin "11") (pinfunction "VCC-_11") (pintype "unspecified"))
      (node (ref "U20") (pin "11") (pinfunction "VCC-_11") (pintype "unspecified"))
      (node (ref "U21") (pin "11") (pinfunction "VCC-_11") (pintype "unspecified"))
      (node (ref "U22") (pin "11") (pinfunction "VCC-_11") (pintype "unspecified"))
      (node (ref "U23") (pin "11") (pinfunction "VCC-_11") (pintype "unspecified"))
      (node (ref "U24") (pin "11") (pinfunction "VCC-_11") (pintype "unspecified"))
    )
    (net (code "4") (name "5V") (class "Default")
      (node (ref "R1") (pin "2") (pinfunction "2_2") (pintype "input"))
      (node (ref "R10") (pin "2") (pinfunction "2_2") (pintype "input"))
      (node (ref "R11") (pin "2") (pinfunction "2_2") (pintype "input"))
      (node (ref "R12") (pin "2") (pinfunction "2_2") (pintype "input"))
      (node (ref "R13") (pin "2") (pinfunction "2_2") (pintype "input"))
      (node (ref "R14") (pin "2") (pinfunction "2_2") (pintype "input"))
      (node (ref "R15") (pin "2") (pinfunction "2_2") (pintype "input"))
      (node (ref "R16") (pin "2") (pinfunction "2_2") (pintype "input"))
      (node (ref "R2") (pin "2") (pinfunction "2_2") (pintype "input"))
      (node (ref "R3") (pin "2") (pinfunction "2_2") (pintype "input"))
      (node (ref "R4") (pin "2") (pinfunction "2_2") (pintype "input"))
      (node (ref "R5") (pin "2") (pinfunction "2_2") (pintype "input"))
      (node (ref "R6") (pin "2") (pinfunction "2_2") (pintype "input"))
      (node (ref "R7") (pin "2") (pinfunction "2_2") (pintype "input"))
      (node (ref "R8") (pin "2") (pinfunction "2_2") (pintype "input"))
      (node (ref "R9") (pin "2") (pinfunction "2_2") (pintype "input"))
      (node (ref "U1") (pin "1") (pinfunction "CCW_1") (pintype "bidirectional"))
      (node (ref "U10") (pin "1") (pinfunction "CCW_1") (pintype "bidirectional"))
      (node (ref "U11") (pin "1") (pinfunction "CCW_1") (pintype "bidirectional"))
      (node (ref "U12") (pin "1") (pinfunction "CCW_1") (pintype "bidirectional"))
      (node (ref "U13") (pin "1") (pinfunction "CCW_1") (pintype "bidirectional"))
      (node (ref "U14") (pin "1") (pinfunction "CCW_1") (pintype "bidirectional"))
      (node (ref "U15") (pin "1") (pinfunction "CCW_1") (pintype "bidirectional"))
      (node (ref "U16") (pin "1") (pinfunction "CCW_1") (pintype "bidirectional"))
      (node (ref "U2") (pin "1") (pinfunction "CCW_1") (pintype "bidirectional"))
      (node (ref "U3") (pin "1") (pinfunction "CCW_1") (pintype "bidirectional"))
      (node (ref "U4") (pin "1") (pinfunction "CCW_1") (pintype "bidirectional"))
      (node (ref "U5") (pin "1") (pinfunction "CCW_1") (pintype "bidirectional"))
      (node (ref "U6") (pin "1") (pinfunction "CCW_1") (pintype "bidirectional"))
      (node (ref "U7") (pin "1") (pinfunction "CCW_1") (pintype "bidirectional"))
      (node (ref "U8") (pin "1") (pinfunction "CCW_1") (pintype "bidirectional"))
      (node (ref "U9") (pin "1") (pinfunction "CCW_1") (pintype "bidirectional"))
    )
    (net (code "5") (name "A0") (class "Default")
      (node (ref "U17") (pin "1") (pinfunction "OUT1_1") (pintype "output"))
      (node (ref "U17") (pin "2") (pinfunction "IN1-_2") (pintype "unspecified"))
      (node (ref "U18") (pin "1") (pinfunction "OUT1_1") (pintype "output"))
      (node (ref "U18") (pin "2") (pinfunction "IN1-_2") (pintype "unspecified"))
      (node (ref "U19") (pin "1") (pinfunction "OUT1_1") (pintype "output"))
      (node (ref "U19") (pin "2") (pinfunction "IN1-_2") (pintype "unspecified"))
      (node (ref "U20") (pin "1") (pinfunction "OUT1_1") (pintype "output"))
      (node (ref "U20") (pin "2") (pinfunction "IN1-_2") (pintype "unspecified"))
      (node (ref "U21") (pin "1") (pinfunction "OUT1_1") (pintype "output"))
      (node (ref "U21") (pin "2") (pinfunction "IN1-_2") (pintype "unspecified"))
      (node (ref "U22") (pin "1") (pinfunction "OUT1_1") (pintype "output"))
      (node (ref "U22") (pin "2") (pinfunction "IN1-_2") (pintype "unspecified"))
      (node (ref "U23") (pin "1") (pinfunction "OUT1_1") (pintype "output"))
      (node (ref "U23") (pin "2") (pinfunction "IN1-_2") (pintype "unspecified"))
      (node (ref "U24") (pin "1") (pinfunction "OUT1_1") (pintype "output"))
      (node (ref "U24") (pin "2") (pinfunction "IN1-_2") (pintype "unspecified"))
    )
    (net (code "6") (name "A1") (class "Default")
      (node (ref "U17") (pin "8") (pinfunction "OUT3_8") (pintype "output"))
      (node (ref "U17") (pin "9") (pinfunction "IN3-_9") (pintype "unspecified"))
      (node (ref "U18") (pin "8") (pinfunction "OUT3_8") (pintype "output"))
      (node (ref "U18") (pin "9") (pinfunction "IN3-_9") (pintype "unspecified"))
      (node (ref "U19") (pin "8") (pinfunction "OUT3_8") (pintype "output"))
      (node (ref "U19") (pin "9") (pinfunction "IN3-_9") (pintype "unspecified"))
      (node (ref "U20") (pin "8") (pinfunction "OUT3_8") (pintype "output"))
      (node (ref "U20") (pin "9") (pinfunction "IN3-_9") (pintype "unspecified"))
      (node (ref "U21") (pin "8") (pinfunction "OUT3_8") (pintype "output"))
      (node (ref "U21") (pin "9") (pinfunction "IN3-_9") (pintype "unspecified"))
      (node (ref "U22") (pin "8") (pinfunction "OUT3_8") (pintype "output"))
      (node (ref "U22") (pin "9") (pinfunction "IN3-_9") (pintype "unspecified"))
      (node (ref "U23") (pin "8") (pinfunction "OUT3_8") (pintype "output"))
      (node (ref "U23") (pin "9") (pinfunction "IN3-_9") (pintype "unspecified"))
      (node (ref "U24") (pin "8") (pinfunction "OUT3_8") (pintype "output"))
      (node (ref "U24") (pin "9") (pinfunction "IN3-_9") (pintype "unspecified"))
    )
    (net (code "7") (name "GND") (class "Default")
      (node (ref "R100") (pin "1") (pinfunction "1_1") (pintype "input"))
      (node (ref "R105") (pin "1") (pinfunction "1_1") (pintype "input"))
      (node (ref "R107") (pin "1") (pinfunction "1_1") (pintype "input"))
      (node (ref "R111") (pin "1") (pinfunction "1_1") (pintype "input"))
      (node (ref "R113") (pin "1") (pinfunction "1_1") (pintype "input"))
      (node (ref "R114") (pin "1") (pinfunction "1_1") (pintype "input"))
      (node (ref "R116") (pin "1") (pinfunction "1_1") (pintype "input"))
      (node (ref "R121") (pin "1") (pinfunction "1_1") (pintype "input"))
      (node (ref "R125") (pin "1") (pinfunction "1_1") (pintype "input"))
      (node (ref "R129") (pin "1") (pinfunction "1_1") (pintype "input"))
      (node (ref "R131") (pin "1") (pinfunction "1_1") (pintype "input"))
      (node (ref "R132") (pin "1") (pinfunction "1_1") (pintype "input"))
      (node (ref "R134") (pin "1") (pinfunction "1_1") (pintype "input"))
      (node (ref "R139") (pin "1") (pinfunction "1_1") (pintype "input"))
      (node (ref "R143") (pin "1") (pinfunction "1_1") (pintype "input"))
      (node (ref "R147") (pin "1") (pinfunction "1_1") (pintype "input"))
      (node (ref "R149") (pin "1") (pinfunction "1_1") (pintype "input"))
      (node (ref "R150") (pin "1") (pinfunction "1_1") (pintype "input"))
      (node (ref "R152") (pin "1") (pinfunction "1_1") (pintype "input"))
      (node (ref "R157") (pin "1") (pinfunction "1_1") (pintype "input"))
      (node (ref "R18") (pin "1") (pinfunction "1_1") (pintype "input"))
      (node (ref "R22") (pin "1") (pinfunction "1_1") (pintype "input"))
      (node (ref "R25") (pin "1") (pinfunction "1_1") (pintype "input"))
      (node (ref "R27") (pin "1") (pinfunction "1_1") (pintype "input"))
      (node (ref "R31") (pin "1") (pinfunction "1_1") (pintype "input"))
      (node (ref "R34") (pin "1") (pinfunction "1_1") (pintype "input"))
      (node (ref "R36") (pin "1") (pinfunction "1_1") (pintype "input"))
      (node (ref "R40") (pin "1") (pinfunction "1_1") (pintype "input"))
      (node (ref "R43") (pin "1") (pinfunction "1_1") (pintype "input"))
      (node (ref "R45") (pin "1") (pinfunction "1_1") (pintype "input"))
      (node (ref "R49") (pin "1") (pinfunction "1_1") (pintype "input"))
      (node (ref "R52") (pin "1") (pinfunction "1_1") (pintype "input"))
      (node (ref "R54") (pin "1") (pinfunction "1_1") (pintype "input"))
      (node (ref "R58") (pin "1") (pinfunction "1_1") (pintype "input"))
      (node (ref "R61") (pin "1") (pinfunction "1_1") (pintype "input"))
      (node (ref "R63") (pin "1") (pinfunction "1_1") (pintype "input"))
      (node (ref "R67") (pin "1") (pinfunction "1_1") (pintype "input"))
      (node (ref "R70") (pin "1") (pinfunction "1_1") (pintype "input"))
      (node (ref "R72") (pin "1") (pinfunction "1_1") (pintype "input"))
      (node (ref "R76") (pin "1") (pinfunction "1_1") (pintype "input"))
      (node (ref "R79") (pin "1") (pinfunction "1_1") (pintype "input"))
      (node (ref "R81") (pin "1") (pinfunction "1_1") (pintype "input"))
      (node (ref "R85") (pin "1") (pinfunction "1_1") (pintype "input"))
      (node (ref "R88") (pin "1") (pinfunction "1_1") (pintype "input"))
      (node (ref "R90") (pin "1") (pinfunction "1_1") (pintype "input"))
      (node (ref "R94") (pin "1") (pinfunction "1_1") (pintype "input"))
      (node (ref "R97") (pin "1") (pinfunction "1_1") (pintype "input"))
      (node (ref "R98") (pin "1") (pinfunction "1_1") (pintype "input"))
      (node (ref "U1") (pin "3") (pinfunction "CW_3") (pintype "bidirectional"))
      (node (ref "U1") (pin "E1") (pinfunction "E_(-)_E1") (pintype "bidirectional"))
      (node (ref "U10") (pin "3") (pinfunction "CW_3") (pintype "bidirectional"))
      (node (ref "U10") (pin "E1") (pinfunction "E_(-)_E1") (pintype "bidirectional"))
      (node (ref "U11") (pin "3") (pinfunction "CW_3") (pintype "bidirectional"))
      (node (ref "U11") (pin "E1") (pinfunction "E_(-)_E1") (pintype "bidirectional"))
      (node (ref "U12") (pin "3") (pinfunction "CW_3") (pintype "bidirectional"))
      (node (ref "U12") (pin "E1") (pinfunction "E_(-)_E1") (pintype "bidirectional"))
      (node (ref "U13") (pin "3") (pinfunction "CW_3") (pintype "bidirectional"))
      (node (ref "U13") (pin "E1") (pinfunction "E_(-)_E1") (pintype "bidirectional"))
      (node (ref "U14") (pin "3") (pinfunction "CW_3") (pintype "bidirectional"))
      (node (ref "U14") (pin "E1") (pinfunction "E_(-)_E1") (pintype "bidirectional"))
      (node (ref "U15") (pin "3") (pinfunction "CW_3") (pintype "bidirectional"))
      (node (ref "U15") (pin "E1") (pinfunction "E_(-)_E1") (pintype "bidirectional"))
      (node (ref "U16") (pin "3") (pinfunction "CW_3") (pintype "bidirectional"))
      (node (ref "U16") (pin "E1") (pinfunction "E_(-)_E1") (pintype "bidirectional"))
      (node (ref "U2") (pin "3") (pinfunction "CW_3") (pintype "bidirectional"))
      (node (ref "U2") (pin "E1") (pinfunction "E_(-)_E1") (pintype "bidirectional"))
      (node (ref "U3") (pin "3") (pinfunction "CW_3") (pintype "bidirectional"))
      (node (ref "U3") (pin "E1") (pinfunction "E_(-)_E1") (pintype "bidirectional"))
      (node (ref "U4") (pin "3") (pinfunction "CW_3") (pintype "bidirectional"))
      (node (ref "U4") (pin "E1") (pinfunction "E_(-)_E1") (pintype "bidirectional"))
      (node (ref "U5") (pin "3") (pinfunction "CW_3") (pintype "bidirectional"))
      (node (ref "U5") (pin "E1") (pinfunction "E_(-)_E1") (pintype "bidirectional"))
      (node (ref "U6") (pin "3") (pinfunction "CW_3") (pintype "bidirectional"))
      (node (ref "U6") (pin "E1") (pinfunction "E_(-)_E1") (pintype "bidirectional"))
      (node (ref "U7") (pin "3") (pinfunction "CW_3") (pintype "bidirectional"))
      (node (ref "U7") (pin "E1") (pinfunction "E_(-)_E1") (pintype "bidirectional"))
      (node (ref "U8") (pin "3") (pinfunction "CW_3") (pintype "bidirectional"))
      (node (ref "U8") (pin "E1") (pinfunction "E_(-)_E1") (pintype "bidirectional"))
      (node (ref "U9") (pin "3") (pinfunction "CW_3") (pintype "bidirectional"))
      (node (ref "U9") (pin "E1") (pinfunction "E_(-)_E1") (pintype "bidirectional"))
    )
    (net (code "8") (name "J0") (class "Default")
      (node (ref "R115") (pin "2") (pinfunction "2_2") (pintype "input"))
      (node (ref "R133") (pin "2") (pinfunction "2_2") (pintype "input"))
      (node (ref "R151") (pin "2") (pinfunction "2_2") (pintype "input"))
      (node (ref "R23") (pin "2") (pinfunction "2_2") (pintype "input"))
      (node (ref "R41") (pin "2") (pinfunction "2_2") (pintype "input"))
      (node (ref "R59") (pin "2") (pinfunction "2_2") (pintype "input"))
      (node (ref "R77") (pin "2") (pinfunction "2_2") (pintype "input"))
      (node (ref "R95") (pin "2") (pinfunction "2_2") (pintype "input"))
    )
    (net (code "9") (name "J1") (class "Default")
      (node (ref "R106") (pin "2") (pinfunction "2_2") (pintype "input"))
      (node (ref "R110") (pin "2") (pinfunction "2_2") (pintype "input"))
      (node (ref "R128") (pin "2") (pinfunction "2_2") (pintype "input"))
      (node (ref "R146") (pin "2") (pinfunction "2_2") (pintype "input"))
      (node (ref "R32") (pin "2") (pinfunction "2_2") (pintype "input"))
      (node (ref "R50") (pin "2") (pinfunction "2_2") (pintype "input"))
      (node (ref "R68") (pin "2") (pinfunction "2_2") (pintype "input"))
      (node (ref "R86") (pin "2") (pinfunction "2_2") (pintype "input"))
    )
    (net (code "10") (name "Net-(R20-Pad1)") (class "Default")
      (node (ref "R20") (pin "1") (pinfunction "1_1") (pintype "input"))
      (node (ref "R24") (pin "1") (pinfunction "1_1") (pintype "input"))
      (node (ref "R25") (pin "2") (pinfunction "2_2") (pintype "input"))
    )
    (net (code "11") (name "Net-(R29-Pad1)") (class "Default")
      (node (ref "R29") (pin "1") (pinfunction "1_1") (pintype "input"))
      (node (ref "R33") (pin "1") (pinfunction "1_1") (pintype "input"))
      (node (ref "R34") (pin "2") (pinfunction "2_2") (pintype "input"))
    )
    (net (code "12") (name "Net-(R38-Pad1)") (class "Default")
      (node (ref "R38") (pin "1") (pinfunction "1_1") (pintype "input"))
      (node (ref "R42") (pin "1") (pinfunction "1_1") (pintype "input"))
      (node (ref "R43") (pin "2") (pinfunction "2_2") (pintype "input"))
    )
    (net (code "13") (name "Net-(R47-Pad1)") (class "Default")
      (node (ref "R47") (pin "1") (pinfunction "1_1") (pintype "input"))
      (node (ref "R51") (pin "1") (pinfunction "1_1") (pintype "input"))
      (node (ref "R52") (pin "2") (pinfunction "2_2") (pintype "input"))
    )
    (net (code "14") (name "Net-(R56-Pad1)") (class "Default")
      (node (ref "R56") (pin "1") (pinfunction "1_1") (pintype "input"))
      (node (ref "R60") (pin "1") (pinfunction "1_1") (pintype "input"))
      (node (ref "R61") (pin "2") (pinfunction "2_2") (pintype "input"))
    )
    (net (code "15") (name "Net-(R65-Pad1)") (class "Default")
      (node (ref "R65") (pin "1") (pinfunction "1_1") (pintype "input"))
      (node (ref "R69") (pin "1") (pinfunction "1_1") (pintype "input"))
      (node (ref "R70") (pin "2") (pinfunction "2_2") (pintype "input"))
    )
    (net (code "16") (name "Net-(R74-Pad1)") (class "Default")
      (node (ref "R74") (pin "1") (pinfunction "1_1") (pintype "input"))
      (node (ref "R78") (pin "1") (pinfunction "1_1") (pintype "input"))
      (node (ref "R79") (pin "2") (pinfunction "2_2") (pintype "input"))
    )
    (net (code "17") (name "Net-(R83-Pad1)") (class "Default")
      (node (ref "R83") (pin "1") (pinfunction "1_1") (pintype "input"))
      (node (ref "R87") (pin "1") (pinfunction "1_1") (pintype "input"))
      (node (ref "R88") (pin "2") (pinfunction "2_2") (pintype "input"))
    )
    (net (code "18") (name "Net-(R92-Pad1)") (class "Default")
      (node (ref "R92") (pin "1") (pinfunction "1_1") (pintype "input"))
      (node (ref "R96") (pin "1") (pinfunction "1_1") (pintype "input"))
      (node (ref "R97") (pin "2") (pinfunction "2_2") (pintype "input"))
    )
    (net (code "19") (name "Net-(R103-Pad1)") (class "Default")
      (node (ref "R103") (pin "1") (pinfunction "1_1") (pintype "input"))
      (node (ref "R104") (pin "1") (pinfunction "1_1") (pintype "input"))
      (node (ref "R105") (pin "2") (pinfunction "2_2") (pintype "input"))
    )
    (net (code "20") (name "Net-(R116-Pad2)") (class "Default")
      (node (ref "R116") (pin "2") (pinfunction "2_2") (pintype "input"))
      (node (ref "R117") (pin "1") (pinfunction "1_1") (pintype "input"))
      (node (ref "R118") (pin "1") (pinfunction "1_1") (pintype "input"))
    )
    (net (code "21") (name "Net-(R120-Pad1)") (class "Default")
      (node (ref "R120") (pin "1") (pinfunction "1_1") (pintype "input"))
      (node (ref "R121") (pin "2") (pinfunction "2_2") (pintype "input"))
      (node (ref "R123") (pin "1") (pinfunction "1_1") (pintype "input"))
    )
    (net (code "22") (name "Net-(R134-Pad2)") (class "Default")
      (node (ref "R134") (pin "2") (pinfunction "2_2") (pintype "input"))
      (node (ref "R135") (pin "1") (pinfunction "1_1") (pintype "input"))
      (node (ref "R136") (pin "1") (pinfunction "1_1") (pintype "input"))
    )
    (net (code "23") (name "Net-(R138-Pad1)") (class "Default")
      (node (ref "R138") (pin "1") (pinfunction "1_1") (pintype "input"))
      (node (ref "R139") (pin "2") (pinfunction "2_2") (pintype "input"))
      (node (ref "R141") (pin "1") (pinfunction "1_1") (pintype "input"))
    )
    (net (code "24") (name "Net-(R152-Pad2)") (class "Default")
      (node (ref "R152") (pin "2") (pinfunction "2_2") (pintype "input"))
      (node (ref "R153") (pin "1") (pinfunction "1_1") (pintype "input"))
      (node (ref "R154") (pin "1") (pinfunction "1_1") (pintype "input"))
    )
    (net (code "25") (name "Net-(R156-Pad1)") (class "Default")
      (node (ref "R156") (pin "1") (pinfunction "1_1") (pintype "input"))
      (node (ref "R157") (pin "2") (pinfunction "2_2") (pintype "input"))
      (node (ref "R159") (pin "1") (pinfunction "1_1") (pintype "input"))
    )
    (net (code "26") (name "Net-(U1-B_(+))") (class "Default")
      (node (ref "R1") (pin "1") (pinfunction "1_1") (pintype "input"))
      (node (ref "U1") (pin "B1") (pinfunction "B_(+)_B1") (pintype "bidirectional"))
    )
    (net (code "27") (name "Net-(U2-B_(+))") (class "Default")
      (node (ref "R2") (pin "1") (pinfunction "1_1") (pintype "input"))
      (node (ref "U2") (pin "B1") (pinfunction "B_(+)_B1") (pintype "bidirectional"))
    )
    (net (code "28") (name "Net-(U3-B_(+))") (class "Default")
      (node (ref "R3") (pin "1") (pinfunction "1_1") (pintype "input"))
      (node (ref "U3") (pin "B1") (pinfunction "B_(+)_B1") (pintype "bidirectional"))
    )
    (net (code "29") (name "Net-(U4-B_(+))") (class "Default")
      (node (ref "R4") (pin "1") (pinfunction "1_1") (pintype "input"))
      (node (ref "U4") (pin "B1") (pinfunction "B_(+)_B1") (pintype "bidirectional"))
    )
    (net (code "30") (name "Net-(U5-B_(+))") (class "Default")
      (node (ref "R5") (pin "1") (pinfunction "1_1") (pintype "input"))
      (node (ref "U5") (pin "B1") (pinfunction "B_(+)_B1") (pintype "bidirectional"))
    )
    (net (code "31") (name "Net-(U6-B_(+))") (class "Default")
      (node (ref "R6") (pin "1") (pinfunction "1_1") (pintype "input"))
      (node (ref "U6") (pin "B1") (pinfunction "B_(+)_B1") (pintype "bidirectional"))
    )
    (net (code "32") (name "Net-(U7-B_(+))") (class "Default")
      (node (ref "R7") (pin "1") (pinfunction "1_1") (pintype "input"))
      (node (ref "U7") (pin "B1") (pinfunction "B_(+)_B1") (pintype "bidirectional"))
    )
    (net (code "33") (name "Net-(U8-B_(+))") (class "Default")
      (node (ref "R8") (pin "1") (pinfunction "1_1") (pintype "input"))
      (node (ref "U8") (pin "B1") (pinfunction "B_(+)_B1") (pintype "bidirectional"))
    )
    (net (code "34") (name "Net-(U9-B_(+))") (class "Default")
      (node (ref "R9") (pin "1") (pinfunction "1_1") (pintype "input"))
      (node (ref "U9") (pin "B1") (pinfunction "B_(+)_B1") (pintype "bidirectional"))
    )
    (net (code "35") (name "Net-(U10-B_(+))") (class "Default")
      (node (ref "R10") (pin "1") (pinfunction "1_1") (pintype "input"))
      (node (ref "U10") (pin "B1") (pinfunction "B_(+)_B1") (pintype "bidirectional"))
    )
    (net (code "36") (name "Net-(U11-B_(+))") (class "Default")
      (node (ref "R11") (pin "1") (pinfunction "1_1") (pintype "input"))
      (node (ref "U11") (pin "B1") (pinfunction "B_(+)_B1") (pintype "bidirectional"))
    )
    (net (code "37") (name "Net-(U12-B_(+))") (class "Default")
      (node (ref "R12") (pin "1") (pinfunction "1_1") (pintype "input"))
      (node (ref "U12") (pin "B1") (pinfunction "B_(+)_B1") (pintype "bidirectional"))
    )
    (net (code "38") (name "Net-(U13-B_(+))") (class "Default")
      (node (ref "R13") (pin "1") (pinfunction "1_1") (pintype "input"))
      (node (ref "U13") (pin "B1") (pinfunction "B_(+)_B1") (pintype "bidirectional"))
    )
    (net (code "39") (name "Net-(U14-B_(+))") (class "Default")
      (node (ref "R14") (pin "1") (pinfunction "1_1") (pintype "input"))
      (node (ref "U14") (pin "B1") (pinfunction "B_(+)_B1") (pintype "bidirectional"))
    )
    (net (code "40") (name "Net-(U15-B_(+))") (class "Default")
      (node (ref "R15") (pin "1") (pinfunction "1_1") (pintype "input"))
      (node (ref "U15") (pin "B1") (pinfunction "B_(+)_B1") (pintype "bidirectional"))
    )
    (net (code "41") (name "Net-(U16-B_(+))") (class "Default")
      (node (ref "R16") (pin "1") (pinfunction "1_1") (pintype "input"))
      (node (ref "U16") (pin "B1") (pinfunction "B_(+)_B1") (pintype "bidirectional"))
    )
    (net (code "42") (name "Net-(U17A-IN1+)") (class "Default")
      (node (ref "R17") (pin "2") (pinfunction "2_2") (pintype "input"))
      (node (ref "R18") (pin "2") (pinfunction "2_2") (pintype "input"))
      (node (ref "U17") (pin "3") (pinfunction "IN1+_3") (pintype "unspecified"))
    )
    (net (code "43") (name "Net-(U17B-IN2+)") (class "Default")
      (node (ref "R19") (pin "2") (pinfunction "2_2") (pintype "input"))
      (node (ref "U17") (pin "5") (pinfunction "IN2+_5") (pintype "unspecified"))
    )
    (net (code "44") (name "Net-(U17B-IN2-)") (class "Default")
      (node (ref "R20") (pin "2") (pinfunction "2_2") (pintype "input"))
      (node (ref "R21") (pin "1") (pinfunction "1_1") (pintype "input"))
      (node (ref "U17") (pin "6") (pinfunction "IN2-_6") (pintype "unspecified"))
    )
    (net (code "45") (name "Net-(U17B-OUT2)") (class "Default")
      (node (ref "R21") (pin "2") (pinfunction "2_2") (pintype "input"))
      (node (ref "R22") (pin "2") (pinfunction "2_2") (pintype "input"))
      (node (ref "R23") (pin "1") (pinfunction "1_1") (pintype "input"))
      (node (ref "U17") (pin "7") (pinfunction "OUT2_7") (pintype "output"))
    )
    (net (code "46") (name "Net-(U17C-IN3+)") (class "Default")
      (node (ref "R26") (pin "2") (pinfunction "2_2") (pintype "input"))
      (node (ref "R27") (pin "2") (pinfunction "2_2") (pintype "input"))
      (node (ref "U17") (pin "10") (pinfunction "IN3+_10") (pintype "unspecified"))
    )
    (net (code "47") (name "Net-(U17D-IN4+)") (class "Default")
      (node (ref "R28") (pin "2") (pinfunction "2_2") (pintype "input"))
      (node (ref "U17") (pin "12") (pinfunction "IN4+_12") (pintype "unspecified"))
    )
    (net (code "48") (name "Net-(U17D-IN4-)") (class "Default")
      (node (ref "R29") (pin "2") (pinfunction "2_2") (pintype "input"))
      (node (ref "R30") (pin "1") (pinfunction "1_1") (pintype "input"))
      (node (ref "U17") (pin "13") (pinfunction "IN4-_13") (pintype "unspecified"))
    )
    (net (code "49") (name "Net-(U17D-OUT4)") (class "Default")
      (node (ref "R30") (pin "2") (pinfunction "2_2") (pintype "input"))
      (node (ref "R31") (pin "2") (pinfunction "2_2") (pintype "input"))
      (node (ref "R32") (pin "1") (pinfunction "1_1") (pintype "input"))
      (node (ref "U17") (pin "14") (pinfunction "OUT4_14") (pintype "output"))
    )
    (net (code "50") (name "Net-(U18A-IN1+)") (class "Default")
      (node (ref "R35") (pin "2") (pinfunction "2_2") (pintype "input"))
      (node (ref "R36") (pin "2") (pinfunction "2_2") (pintype "input"))
      (node (ref "U18") (pin "3") (pinfunction "IN1+_3") (pintype "unspecified"))
    )
    (net (code "51") (name "Net-(U18B-IN2+)") (class "Default")
      (node (ref "R37") (pin "2") (pinfunction "2_2") (pintype "input"))
      (node (ref "U18") (pin "5") (pinfunction "IN2+_5") (pintype "unspecified"))
    )
    (net (code "52") (name "Net-(U18B-IN2-)") (class "Default")
      (node (ref "R38") (pin "2") (pinfunction "2_2") (pintype "input"))
      (node (ref "R39") (pin "1") (pinfunction "1_1") (pintype "input"))
      (node (ref "U18") (pin "6") (pinfunction "IN2-_6") (pintype "unspecified"))
    )
    (net (code "53") (name "Net-(U18B-OUT2)") (class "Default")
      (node (ref "R39") (pin "2") (pinfunction "2_2") (pintype "input"))
      (node (ref "R40") (pin "2") (pinfunction "2_2") (pintype "input"))
      (node (ref "R41") (pin "1") (pinfunction "1_1") (pintype "input"))
      (node (ref "U18") (pin "7") (pinfunction "OUT2_7") (pintype "output"))
    )
    (net (code "54") (name "Net-(U18C-IN3+)") (class "Default")
      (node (ref "R44") (pin "2") (pinfunction "2_2") (pintype "input"))
      (node (ref "R45") (pin "2") (pinfunction "2_2") (pintype "input"))
      (node (ref "U18") (pin "10") (pinfunction "IN3+_10") (pintype "unspecified"))
    )
    (net (code "55") (name "Net-(U18D-IN4+)") (class "Default")
      (node (ref "R46") (pin "2") (pinfunction "2_2") (pintype "input"))
      (node (ref "U18") (pin "12") (pinfunction "IN4+_12") (pintype "unspecified"))
    )
    (net (code "56") (name "Net-(U18D-IN4-)") (class "Default")
      (node (ref "R47") (pin "2") (pinfunction "2_2") (pintype "input"))
      (node (ref "R48") (pin "1") (pinfunction "1_1") (pintype "input"))
      (node (ref "U18") (pin "13") (pinfunction "IN4-_13") (pintype "unspecified"))
    )
    (net (code "57") (name "Net-(U18D-OUT4)") (class "Default")
      (node (ref "R48") (pin "2") (pinfunction "2_2") (pintype "input"))
      (node (ref "R49") (pin "2") (pinfunction "2_2") (pintype "input"))
      (node (ref "R50") (pin "1") (pinfunction "1_1") (pintype "input"))
      (node (ref "U18") (pin "14") (pinfunction "OUT4_14") (pintype "output"))
    )
    (net (code "58") (name "Net-(U19A-IN1+)") (class "Default")
      (node (ref "R53") (pin "2") (pinfunction "2_2") (pintype "input"))
      (node (ref "R54") (pin "2") (pinfunction "2_2") (pintype "input"))
      (node (ref "U19") (pin "3") (pinfunction "IN1+_3") (pintype "unspecified"))
    )
    (net (code "59") (name "Net-(U19B-IN2+)") (class "Default")
      (node (ref "R55") (pin "2") (pinfunction "2_2") (pintype "input"))
      (node (ref "U19") (pin "5") (pinfunction "IN2+_5") (pintype "unspecified"))
    )
    (net (code "60") (name "Net-(U19B-IN2-)") (class "Default")
      (node (ref "R56") (pin "2") (pinfunction "2_2") (pintype "input"))
      (node (ref "R57") (pin "1") (pinfunction "1_1") (pintype "input"))
      (node (ref "U19") (pin "6") (pinfunction "IN2-_6") (pintype "unspecified"))
    )
    (net (code "61") (name "Net-(U19B-OUT2)") (class "Default")
      (node (ref "R57") (pin "2") (pinfunction "2_2") (pintype "input"))
      (node (ref "R58") (pin "2") (pinfunction "2_2") (pintype "input"))
      (node (ref "R59") (pin "1") (pinfunction "1_1") (pintype "input"))
      (node (ref "U19") (pin "7") (pinfunction "OUT2_7") (pintype "output"))
    )
    (net (code "62") (name "Net-(U19C-IN3+)") (class "Default")
      (node (ref "R62") (pin "2") (pinfunction "2_2") (pintype "input"))
      (node (ref "R63") (pin "2") (pinfunction "2_2") (pintype "input"))
      (node (ref "U19") (pin "10") (pinfunction "IN3+_10") (pintype "unspecified"))
    )
    (net (code "63") (name "Net-(U19D-IN4+)") (class "Default")
      (node (ref "R64") (pin "2") (pinfunction "2_2") (pintype "input"))
      (node (ref "U19") (pin "12") (pinfunction "IN4+_12") (pintype "unspecified"))
    )
    (net (code "64") (name "Net-(U19D-IN4-)") (class "Default")
      (node (ref "R65") (pin "2") (pinfunction "2_2") (pintype "input"))
      (node (ref "R66") (pin "1") (pinfunction "1_1") (pintype "input"))
      (node (ref "U19") (pin "13") (pinfunction "IN4-_13") (pintype "unspecified"))
    )
    (net (code "65") (name "Net-(U19D-OUT4)") (class "Default")
      (node (ref "R66") (pin "2") (pinfunction "2_2") (pintype "input"))
      (node (ref "R67") (pin "2") (pinfunction "2_2") (pintype "input"))
      (node (ref "R68") (pin "1") (pinfunction "1_1") (pintype "input"))
      (node (ref "U19") (pin "14") (pinfunction "OUT4_14") (pintype "output"))
    )
    (net (code "66") (name "Net-(U20A-IN1+)") (class "Default")
      (node (ref "R71") (pin "2") (pinfunction "2_2") (pintype "input"))
      (node (ref "R72") (pin "2") (pinfunction "2_2") (pintype "input"))
      (node (ref "U20") (pin "3") (pinfunction "IN1+_3") (pintype "unspecified"))
    )
    (net (code "67") (name "Net-(U20B-IN2+)") (class "Default")
      (node (ref "R73") (pin "2") (pinfunction "2_2") (pintype "input"))
      (node (ref "U20") (pin "5") (pinfunction "IN2+_5") (pintype "unspecified"))
    )
    (net (code "68") (name "Net-(U20B-IN2-)") (class "Default")
      (node (ref "R74") (pin "2") (pinfunction "2_2") (pintype "input"))
      (node (ref "R75") (pin "1") (pinfunction "1_1") (pintype "input"))
      (node (ref "U20") (pin "6") (pinfunction "IN2-_6") (pintype "unspecified"))
    )
    (net (code "69") (name "Net-(U20B-OUT2)") (class "Default")
      (node (ref "R75") (pin "2") (pinfunction "2_2") (pintype "input"))
      (node (ref "R76") (pin "2") (pinfunction "2_2") (pintype "input"))
      (node (ref "R77") (pin "1") (pinfunction "1_1") (pintype "input"))
      (node (ref "U20") (pin "7") (pinfunction "OUT2_7") (pintype "output"))
    )
    (net (code "70") (name "Net-(U20C-IN3+)") (class "Default")
      (node (ref "R80") (pin "2") (pinfunction "2_2") (pintype "input"))
      (node (ref "R81") (pin "2") (pinfunction "2_2") (pintype "input"))
      (node (ref "U20") (pin "10") (pinfunction "IN3+_10") (pintype "unspecified"))
    )
    (net (code "71") (name "Net-(U20D-IN4+)") (class "Default")
      (node (ref "R82") (pin "2") (pinfunction "2_2") (pintype "input"))
      (node (ref "U20") (pin "12") (pinfunction "IN4+_12") (pintype "unspecified"))
    )
    (net (code "72") (name "Net-(U20D-IN4-)") (class "Default")
      (node (ref "R83") (pin "2") (pinfunction "2_2") (pintype "input"))
      (node (ref "R84") (pin "1") (pinfunction "1_1") (pintype "input"))
      (node (ref "U20") (pin "13") (pinfunction "IN4-_13") (pintype "unspecified"))
    )
    (net (code "73") (name "Net-(U20D-OUT4)") (class "Default")
      (node (ref "R84") (pin "2") (pinfunction "2_2") (pintype "input"))
      (node (ref "R85") (pin "2") (pinfunction "2_2") (pintype "input"))
      (node (ref "R86") (pin "1") (pinfunction "1_1") (pintype "input"))
      (node (ref "U20") (pin "14") (pinfunction "OUT4_14") (pintype "output"))
    )
    (net (code "74") (name "Net-(U21A-IN1+)") (class "Default")
      (node (ref "R89") (pin "2") (pinfunction "2_2") (pintype "input"))
      (node (ref "R90") (pin "2") (pinfunction "2_2") (pintype "input"))
      (node (ref "U21") (pin "3") (pinfunction "IN1+_3") (pintype "unspecified"))
    )
    (net (code "75") (name "Net-(U21B-IN2+)") (class "Default")
      (node (ref "R91") (pin "2") (pinfunction "2_2") (pintype "input"))
      (node (ref "U21") (pin "5") (pinfunction "IN2+_5") (pintype "unspecified"))
    )
    (net (code "76") (name "Net-(U21B-IN2-)") (class "Default")
      (node (ref "R92") (pin "2") (pinfunction "2_2") (pintype "input"))
      (node (ref "R93") (pin "1") (pinfunction "1_1") (pintype "input"))
      (node (ref "U21") (pin "6") (pinfunction "IN2-_6") (pintype "unspecified"))
    )
    (net (code "77") (name "Net-(U21B-OUT2)") (class "Default")
      (node (ref "R93") (pin "2") (pinfunction "2_2") (pintype "input"))
      (node (ref "R94") (pin "2") (pinfunction "2_2") (pintype "input"))
      (node (ref "R95") (pin "1") (pinfunction "1_1") (pintype "input"))
      (node (ref "U21") (pin "7") (pinfunction "OUT2_7") (pintype "output"))
    )
    (net (code "78") (name "Net-(U21C-IN3+)") (class "Default")
      (node (ref "R98") (pin "2") (pinfunction "2_2") (pintype "input"))
      (node (ref "R99") (pin "2") (pinfunction "2_2") (pintype "input"))
      (node (ref "U21") (pin "10") (pinfunction "IN3+_10") (pintype "unspecified"))
    )
    (net (code "79") (name "Net-(U21D-IN4+)") (class "Default")
      (node (ref "R102") (pin "2") (pinfunction "2_2") (pintype "input"))
      (node (ref "U21") (pin "12") (pinfunction "IN4+_12") (pintype "unspecified"))
    )
    (net (code "80") (name "Net-(U21D-IN4-)") (class "Default")
      (node (ref "R101") (pin "1") (pinfunction "1_1") (pintype "input"))
      (node (ref "R103") (pin "2") (pinfunction "2_2") (pintype "input"))
      (node (ref "U21") (pin "13") (pinfunction "IN4-_13") (pintype "unspecified"))
    )
    (net (code "81") (name "Net-(U21D-OUT4)") (class "Default")
      (node (ref "R100") (pin "2") (pinfunction "2_2") (pintype "input"))
      (node (ref "R101") (pin "2") (pinfunction "2_2") (pintype "input"))
      (node (ref "R106") (pin "1") (pinfunction "1_1") (pintype "input"))
      (node (ref "U21") (pin "14") (pinfunction "OUT4_14") (pintype "output"))
    )
    (net (code "82") (name "Net-(U22A-IN1+)") (class "Default")
      (node (ref "R113") (pin "2") (pinfunction "2_2") (pintype "input"))
      (node (ref "R122") (pin "2") (pinfunction "2_2") (pintype "input"))
      (node (ref "U22") (pin "3") (pinfunction "IN1+_3") (pintype "unspecified"))
    )
    (net (code "83") (name "Net-(U22B-IN2+)") (class "Default")
      (node (ref "R108") (pin "2") (pinfunction "2_2") (pintype "input"))
      (node (ref "U22") (pin "5") (pinfunction "IN2+_5") (pintype "unspecified"))
    )
    (net (code "84") (name "Net-(U22B-IN2-)") (class "Default")
      (node (ref "R109") (pin "1") (pinfunction "1_1") (pintype "input"))
      (node (ref "R120") (pin "2") (pinfunction "2_2") (pintype "input"))
      (node (ref "U22") (pin "6") (pinfunction "IN2-_6") (pintype "unspecified"))
    )
    (net (code "85") (name "Net-(U22B-OUT2)") (class "Default")
      (node (ref "R107") (pin "2") (pinfunction "2_2") (pintype "input"))
      (node (ref "R109") (pin "2") (pinfunction "2_2") (pintype "input"))
      (node (ref "R115") (pin "1") (pinfunction "1_1") (pintype "input"))
      (node (ref "U22") (pin "7") (pinfunction "OUT2_7") (pintype "output"))
    )
    (net (code "86") (name "Net-(U22C-IN3+)") (class "Default")
      (node (ref "R114") (pin "2") (pinfunction "2_2") (pintype "input"))
      (node (ref "R119") (pin "2") (pinfunction "2_2") (pintype "input"))
      (node (ref "U22") (pin "10") (pinfunction "IN3+_10") (pintype "unspecified"))
    )
    (net (code "87") (name "Net-(U22D-IN4+)") (class "Default")
      (node (ref "R112") (pin "2") (pinfunction "2_2") (pintype "input"))
      (node (ref "U22") (pin "12") (pinfunction "IN4+_12") (pintype "unspecified"))
    )
    (net (code "88") (name "Net-(U22D-IN4-)") (class "Default")
      (node (ref "R117") (pin "2") (pinfunction "2_2") (pintype "input"))
      (node (ref "R124") (pin "1") (pinfunction "1_1") (pintype "input"))
      (node (ref "U22") (pin "13") (pinfunction "IN4-_13") (pintype "unspecified"))
    )
    (net (code "89") (name "Net-(U22D-OUT4)") (class "Default")
      (node (ref "R110") (pin "1") (pinfunction "1_1") (pintype "input"))
      (node (ref "R111") (pin "2") (pinfunction "2_2") (pintype "input"))
      (node (ref "R124") (pin "2") (pinfunction "2_2") (pintype "input"))
      (node (ref "U22") (pin "14") (pinfunction "OUT4_14") (pintype "output"))
    )
    (net (code "90") (name "Net-(U23A-IN1+)") (class "Default")
      (node (ref "R131") (pin "2") (pinfunction "2_2") (pintype "input"))
      (node (ref "R140") (pin "2") (pinfunction "2_2") (pintype "input"))
      (node (ref "U23") (pin "3") (pinfunction "IN1+_3") (pintype "unspecified"))
    )
    (net (code "91") (name "Net-(U23B-IN2+)") (class "Default")
      (node (ref "R126") (pin "2") (pinfunction "2_2") (pintype "input"))
      (node (ref "U23") (pin "5") (pinfunction "IN2+_5") (pintype "unspecified"))
    )
    (net (code "92") (name "Net-(U23B-IN2-)") (class "Default")
      (node (ref "R127") (pin "1") (pinfunction "1_1") (pintype "input"))
      (node (ref "R138") (pin "2") (pinfunction "2_2") (pintype "input"))
      (node (ref "U23") (pin "6") (pinfunction "IN2-_6") (pintype "unspecified"))
    )
    (net (code "93") (name "Net-(U23B-OUT2)") (class "Default")
      (node (ref "R125") (pin "2") (pinfunction "2_2") (pintype "input"))
      (node (ref "R127") (pin "2") (pinfunction "2_2") (pintype "input"))
      (node (ref "R133") (pin "1") (pinfunction "1_1") (pintype "input"))
      (node (ref "U23") (pin "7") (pinfunction "OUT2_7") (pintype "output"))
    )
    (net (code "94") (name "Net-(U23C-IN3+)") (class "Default")
      (node (ref "R132") (pin "2") (pinfunction "2_2") (pintype "input"))
      (node (ref "R137") (pin "2") (pinfunction "2_2") (pintype "input"))
      (node (ref "U23") (pin "10") (pinfunction "IN3+_10") (pintype "unspecified"))
    )
    (net (code "95") (name "Net-(U23D-IN4+)") (class "Default")
      (node (ref "R130") (pin "2") (pinfunction "2_2") (pintype "input"))
      (node (ref "U23") (pin "12") (pinfunction "IN4+_12") (pintype "unspecified"))
    )
    (net (code "96") (name "Net-(U23D-IN4-)") (class "Default")
      (node (ref "R135") (pin "2") (pinfunction "2_2") (pintype "input"))
      (node (ref "R142") (pin "1") (pinfunction "1_1") (pintype "input"))
      (node (ref "U23") (pin "13") (pinfunction "IN4-_13") (pintype "unspecified"))
    )
    (net (code "97") (name "Net-(U23D-OUT4)") (class "Default")
      (node (ref "R128") (pin "1") (pinfunction "1_1") (pintype "input"))
      (node (ref "R129") (pin "2") (pinfunction "2_2") (pintype "input"))
      (node (ref "R142") (pin "2") (pinfunction "2_2") (pintype "input"))
      (node (ref "U23") (pin "14") (pinfunction "OUT4_14") (pintype "output"))
    )
    (net (code "98") (name "Net-(U24A-IN1+)") (class "Default")
      (node (ref "R149") (pin "2") (pinfunction "2_2") (pintype "input"))
      (node (ref "R158") (pin "2") (pinfunction "2_2") (pintype "input"))
      (node (ref "U24") (pin "3") (pinfunction "IN1+_3") (pintype "unspecified"))
    )
    (net (code "99") (name "Net-(U24B-IN2+)") (class "Default")
      (node (ref "R144") (pin "2") (pinfunction "2_2") (pintype "input"))
      (node (ref "U24") (pin "5") (pinfunction "IN2+_5") (pintype "unspecified"))
    )
    (net (code "100") (name "Net-(U24B-IN2-)") (class "Default")
      (node (ref "R145") (pin "1") (pinfunction "1_1") (pintype "input"))
      (node (ref "R156") (pin "2") (pinfunction "2_2") (pintype "input"))
      (node (ref "U24") (pin "6") (pinfunction "IN2-_6") (pintype "unspecified"))
    )
    (net (code "101") (name "Net-(U24B-OUT2)") (class "Default")
      (node (ref "R143") (pin "2") (pinfunction "2_2") (pintype "input"))
      (node (ref "R145") (pin "2") (pinfunction "2_2") (pintype "input"))
      (node (ref "R151") (pin "1") (pinfunction "1_1") (pintype "input"))
      (node (ref "U24") (pin "7") (pinfunction "OUT2_7") (pintype "output"))
    )
    (net (code "102") (name "Net-(U24C-IN3+)") (class "Default")
      (node (ref "R150") (pin "2") (pinfunction "2_2") (pintype "input"))
      (node (ref "R155") (pin "2") (pinfunction "2_2") (pintype "input"))
      (node (ref "U24") (pin "10") (pinfunction "IN3+_10") (pintype "unspecified"))
    )
    (net (code "103") (name "Net-(U24D-IN4+)") (class "Default")
      (node (ref "R148") (pin "2") (pinfunction "2_2") (pintype "input"))
      (node (ref "U24") (pin "12") (pinfunction "IN4+_12") (pintype "unspecified"))
    )
    (net (code "104") (name "Net-(U24D-IN4-)") (class "Default")
      (node (ref "R153") (pin "2") (pinfunction "2_2") (pintype "input"))
      (node (ref "R160") (pin "1") (pinfunction "1_1") (pintype "input"))
      (node (ref "U24") (pin "13") (pinfunction "IN4-_13") (pintype "unspecified"))
    )
    (net (code "105") (name "Net-(U24D-OUT4)") (class "Default")
      (node (ref "R146") (pin "1") (pinfunction "1_1") (pintype "input"))
      (node (ref "R147") (pin "2") (pinfunction "2_2") (pintype "input"))
      (node (ref "R160") (pin "2") (pinfunction "2_2") (pintype "input"))
      (node (ref "U24") (pin "14") (pinfunction "OUT4_14") (pintype "output"))
    )
    (net (code "106") (name "P0") (class "Default")
      (node (ref "R108") (pin "1") (pinfunction "1_1") (pintype "input"))
      (node (ref "R122") (pin "1") (pinfunction "1_1") (pintype "input"))
      (node (ref "R126") (pin "1") (pinfunction "1_1") (pintype "input"))
      (node (ref "R140") (pin "1") (pinfunction "1_1") (pintype "input"))
      (node (ref "R144") (pin "1") (pinfunction "1_1") (pintype "input"))
      (node (ref "R158") (pin "1") (pinfunction "1_1") (pintype "input"))
      (node (ref "R17") (pin "1") (pinfunction "1_1") (pintype "input"))
      (node (ref "R19") (pin "1") (pinfunction "1_1") (pintype "input"))
      (node (ref "R35") (pin "1") (pinfunction "1_1") (pintype "input"))
      (node (ref "R37") (pin "1") (pinfunction "1_1") (pintype "input"))
      (node (ref "R53") (pin "1") (pinfunction "1_1") (pintype "input"))
      (node (ref "R55") (pin "1") (pinfunction "1_1") (pintype "input"))
      (node (ref "R71") (pin "1") (pinfunction "1_1") (pintype "input"))
      (node (ref "R73") (pin "1") (pinfunction "1_1") (pintype "input"))
      (node (ref "R89") (pin "1") (pinfunction "1_1") (pintype "input"))
      (node (ref "R91") (pin "1") (pinfunction "1_1") (pintype "input"))
      (node (ref "U1") (pin "2") (pinfunction "WIPER_2") (pintype "bidirectional"))
    )
    (net (code "107") (name "P1") (class "Default")
      (node (ref "R102") (pin "1") (pinfunction "1_1") (pintype "input"))
      (node (ref "R112") (pin "1") (pinfunction "1_1") (pintype "input"))
      (node (ref "R119") (pin "1") (pinfunction "1_1") (pintype "input"))
      (node (ref "R130") (pin "1") (pinfunction "1_1") (pintype "input"))
      (node (ref "R137") (pin "1") (pinfunction "1_1") (pintype "input"))
      (node (ref "R148") (pin "1") (pinfunction "1_1") (pintype "input"))
      (node (ref "R155") (pin "1") (pinfunction "1_1") (pintype "input"))
      (node (ref "R26") (pin "1") (pinfunction "1_1") (pintype "input"))
      (node (ref "R28") (pin "1") (pinfunction "1_1") (pintype "input"))
      (node (ref "R44") (pin "1") (pinfunction "1_1") (pintype "input"))
      (node (ref "R46") (pin "1") (pinfunction "1_1") (pintype "input"))
      (node (ref "R62") (pin "1") (pinfunction "1_1") (pintype "input"))
      (node (ref "R64") (pin "1") (pinfunction "1_1") (pintype "input"))
      (node (ref "R80") (pin "1") (pinfunction "1_1") (pintype "input"))
      (node (ref "R82") (pin "1") (pinfunction "1_1") (pintype "input"))
      (node (ref "R99") (pin "1") (pinfunction "1_1") (pintype "input"))
      (node (ref "U2") (pin "2") (pinfunction "WIPER_2") (pintype "bidirectional"))
    )
    (net (code "108") (name "P2") (class "Default")
      (node (ref "U3") (pin "2") (pinfunction "WIPER_2") (pintype "bidirectional"))
    )
    (net (code "109") (name "P3") (class "Default")
      (node (ref "U4") (pin "2") (pinfunction "WIPER_2") (pintype "bidirectional"))
    )
    (net (code "110") (name "P4") (class "Default")
      (node (ref "U5") (pin "2") (pinfunction "WIPER_2") (pintype "bidirectional"))
    )
    (net (code "111") (name "P5") (class "Default")
      (node (ref "U6") (pin "2") (pinfunction "WIPER_2") (pintype "bidirectional"))
    )
    (net (code "112") (name "P6") (class "Default")
      (node (ref "U7") (pin "2") (pinfunction "WIPER_2") (pintype "bidirectional"))
    )
    (net (code "113") (name "P7") (class "Default")
      (node (ref "U8") (pin "2") (pinfunction "WIPER_2") (pintype "bidirectional"))
    )
    (net (code "114") (name "P8") (class "Default")
      (node (ref "U9") (pin "2") (pinfunction "WIPER_2") (pintype "bidirectional"))
    )
    (net (code "115") (name "P9") (class "Default")
      (node (ref "U10") (pin "2") (pinfunction "WIPER_2") (pintype "bidirectional"))
    )
    (net (code "116") (name "P10") (class "Default")
      (node (ref "U11") (pin "2") (pinfunction "WIPER_2") (pintype "bidirectional"))
    )
    (net (code "117") (name "P11") (class "Default")
      (node (ref "U12") (pin "2") (pinfunction "WIPER_2") (pintype "bidirectional"))
    )
    (net (code "118") (name "P12") (class "Default")
      (node (ref "U13") (pin "2") (pinfunction "WIPER_2") (pintype "bidirectional"))
    )
    (net (code "119") (name "P13") (class "Default")
      (node (ref "U14") (pin "2") (pinfunction "WIPER_2") (pintype "bidirectional"))
    )
    (net (code "120") (name "P14") (class "Default")
      (node (ref "U15") (pin "2") (pinfunction "WIPER_2") (pintype "bidirectional"))
    )
    (net (code "121") (name "P15") (class "Default")
      (node (ref "U16") (pin "2") (pinfunction "WIPER_2") (pintype "bidirectional"))
    )
    (net (code "122") (name "unconnected-(U1-DUMMY_TERMINAL-PadL1)") (class "Default")
      (node (ref "U1") (pin "L1") (pinfunction "DUMMY_TERMINAL_L1") (pintype "bidirectional+no_connect"))
    )
    (net (code "123") (name "unconnected-(U2-DUMMY_TERMINAL-PadL1)") (class "Default")
      (node (ref "U2") (pin "L1") (pinfunction "DUMMY_TERMINAL_L1") (pintype "bidirectional+no_connect"))
    )
    (net (code "124") (name "unconnected-(U3-DUMMY_TERMINAL-PadL1)") (class "Default")
      (node (ref "U3") (pin "L1") (pinfunction "DUMMY_TERMINAL_L1") (pintype "bidirectional+no_connect"))
    )
    (net (code "125") (name "unconnected-(U4-DUMMY_TERMINAL-PadL1)") (class "Default")
      (node (ref "U4") (pin "L1") (pinfunction "DUMMY_TERMINAL_L1") (pintype "bidirectional+no_connect"))
    )
    (net (code "126") (name "unconnected-(U5-DUMMY_TERMINAL-PadL1)") (class "Default")
      (node (ref "U5") (pin "L1") (pinfunction "DUMMY_TERMINAL_L1") (pintype "bidirectional+no_connect"))
    )
    (net (code "127") (name "unconnected-(U6-DUMMY_TERMINAL-PadL1)") (class "Default")
      (node (ref "U6") (pin "L1") (pinfunction "DUMMY_TERMINAL_L1") (pintype "bidirectional+no_connect"))
    )
    (net (code "128") (name "unconnected-(U7-DUMMY_TERMINAL-PadL1)") (class "Default")
      (node (ref "U7") (pin "L1") (pinfunction "DUMMY_TERMINAL_L1") (pintype "bidirectional+no_connect"))
    )
    (net (code "129") (name "unconnected-(U8-DUMMY_TERMINAL-PadL1)") (class "Default")
      (node (ref "U8") (pin "L1") (pinfunction "DUMMY_TERMINAL_L1") (pintype "bidirectional+no_connect"))
    )
    (net (code "130") (name "unconnected-(U9-DUMMY_TERMINAL-PadL1)") (class "Default")
      (node (ref "U9") (pin "L1") (pinfunction "DUMMY_TERMINAL_L1") (pintype "bidirectional+no_connect"))
    )
    (net (code "131") (name "unconnected-(U10-DUMMY_TERMINAL-PadL1)") (class "Default")
      (node (ref "U10") (pin "L1") (pinfunction "DUMMY_TERMINAL_L1") (pintype "bidirectional+no_connect"))
    )
    (net (code "132") (name "unconnected-(U11-DUMMY_TERMINAL-PadL1)") (class "Default")
      (node (ref "U11") (pin "L1") (pinfunction "DUMMY_TERMINAL_L1") (pintype "bidirectional+no_connect"))
    )
    (net (code "133") (name "unconnected-(U12-DUMMY_TERMINAL-PadL1)") (class "Default")
      (node (ref "U12") (pin "L1") (pinfunction "DUMMY_TERMINAL_L1") (pintype "bidirectional+no_connect"))
    )
    (net (code "134") (name "unconnected-(U13-DUMMY_TERMINAL-PadL1)") (class "Default")
      (node (ref "U13") (pin "L1") (pinfunction "DUMMY_TERMINAL_L1") (pintype "bidirectional+no_connect"))
    )
    (net (code "135") (name "unconnected-(U14-DUMMY_TERMINAL-PadL1)") (class "Default")
      (node (ref "U14") (pin "L1") (pinfunction "DUMMY_TERMINAL_L1") (pintype "bidirectional+no_connect"))
    )
    (net (code "136") (name "unconnected-(U15-DUMMY_TERMINAL-PadL1)") (class "Default")
      (node (ref "U15") (pin "L1") (pinfunction "DUMMY_TERMINAL_L1") (pintype "bidirectional+no_connect"))
    )
    (net (code "137") (name "unconnected-(U16-DUMMY_TERMINAL-PadL1)") (class "Default")
      (node (ref "U16") (pin "L1") (pinfunction "DUMMY_TERMINAL_L1") (pintype "bidirectional+no_connect"))
    )
  )
)
